# toyotune_3s_coolrunner.net
KiCad netlist of a schematic drawn in EAGLE
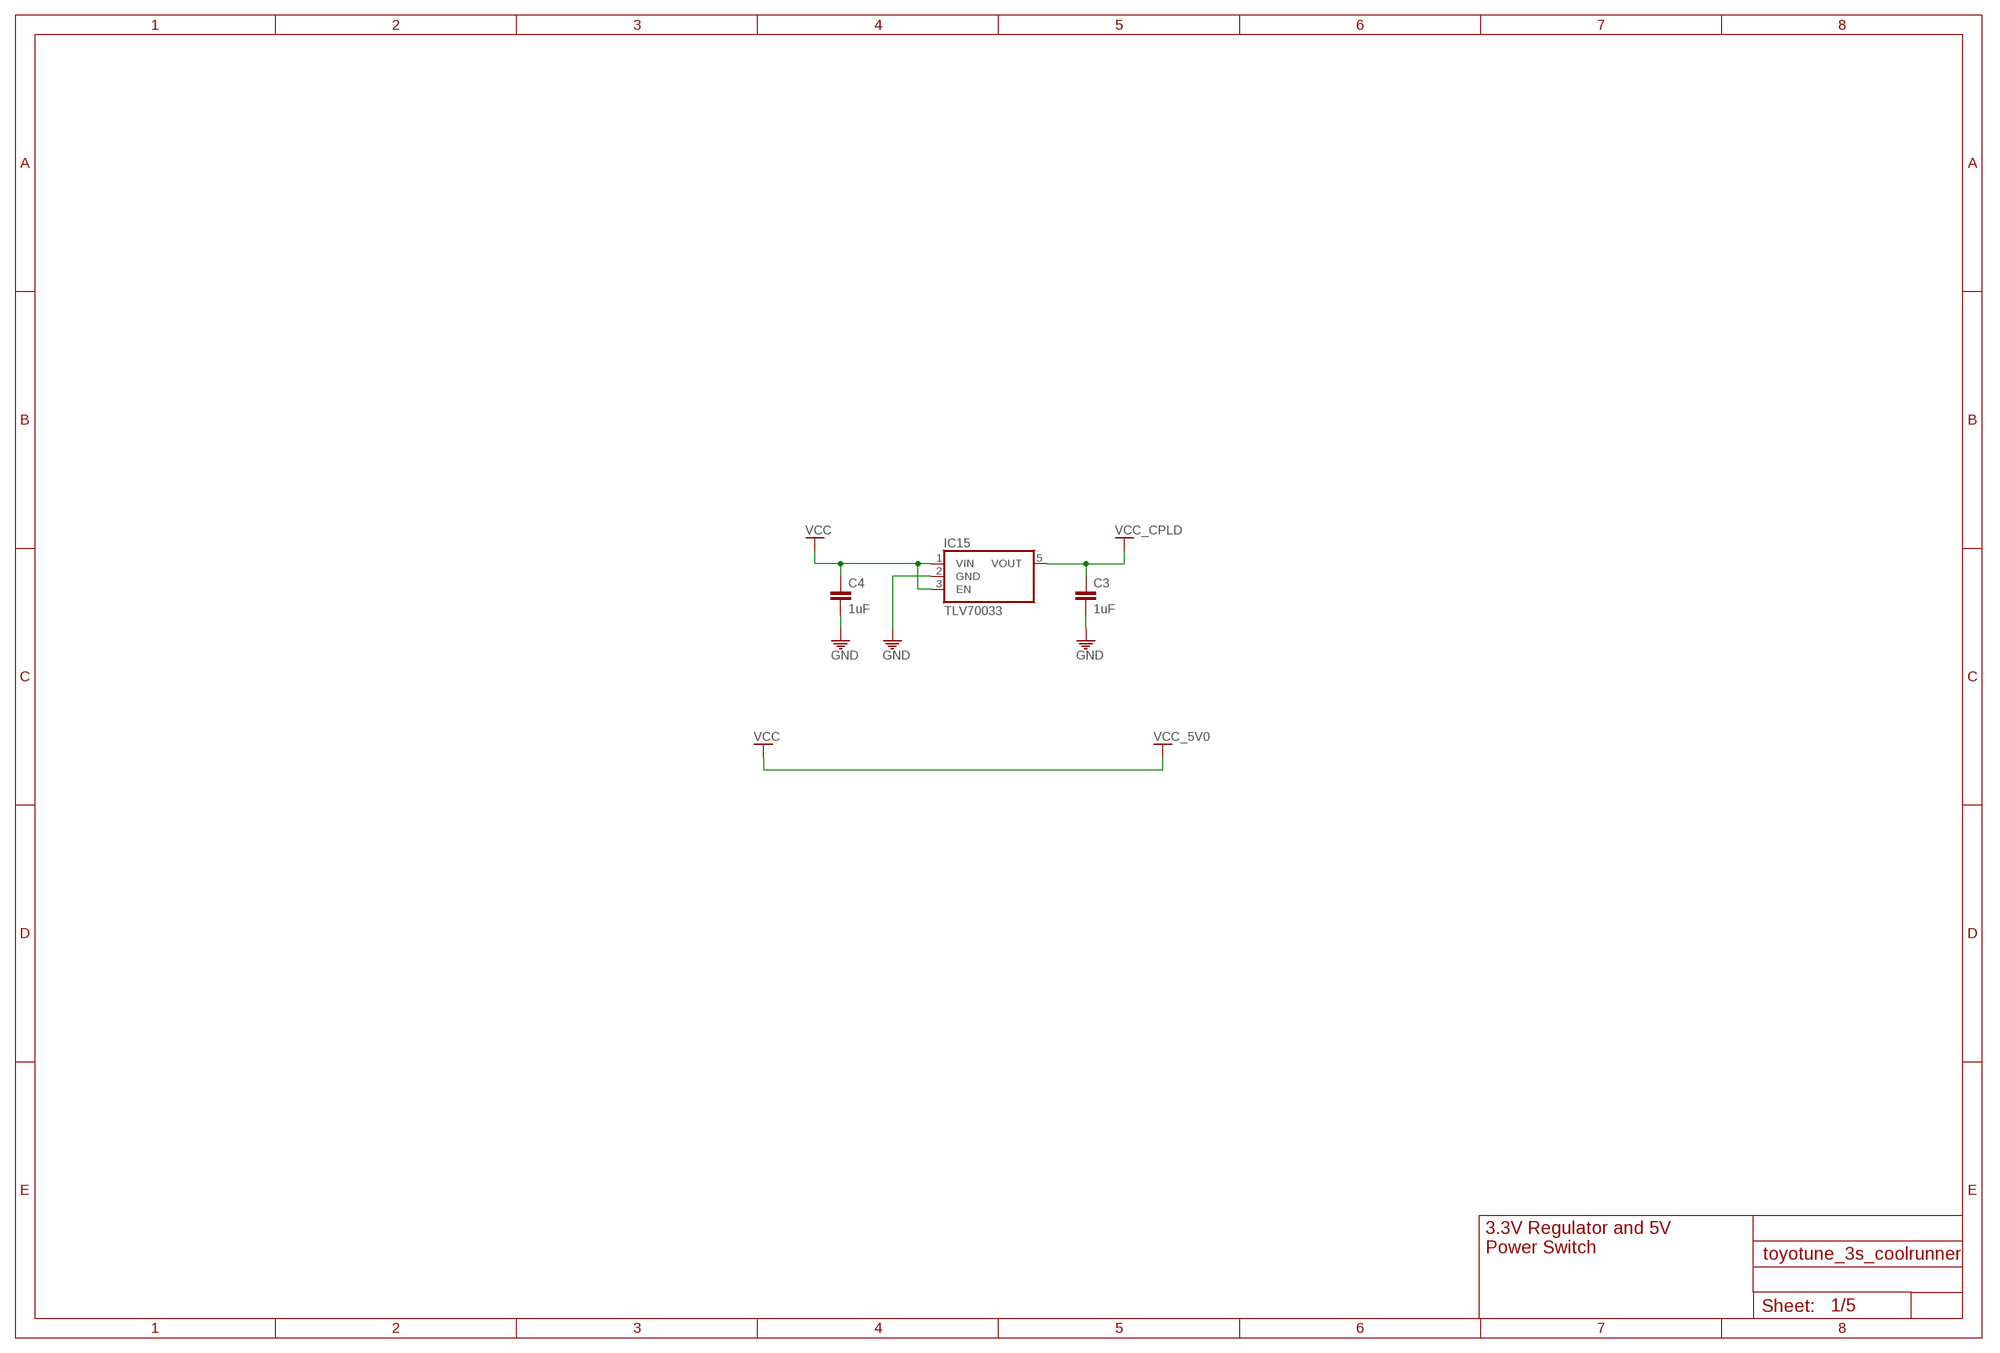
[diagram p0: schematic, sheet 1]
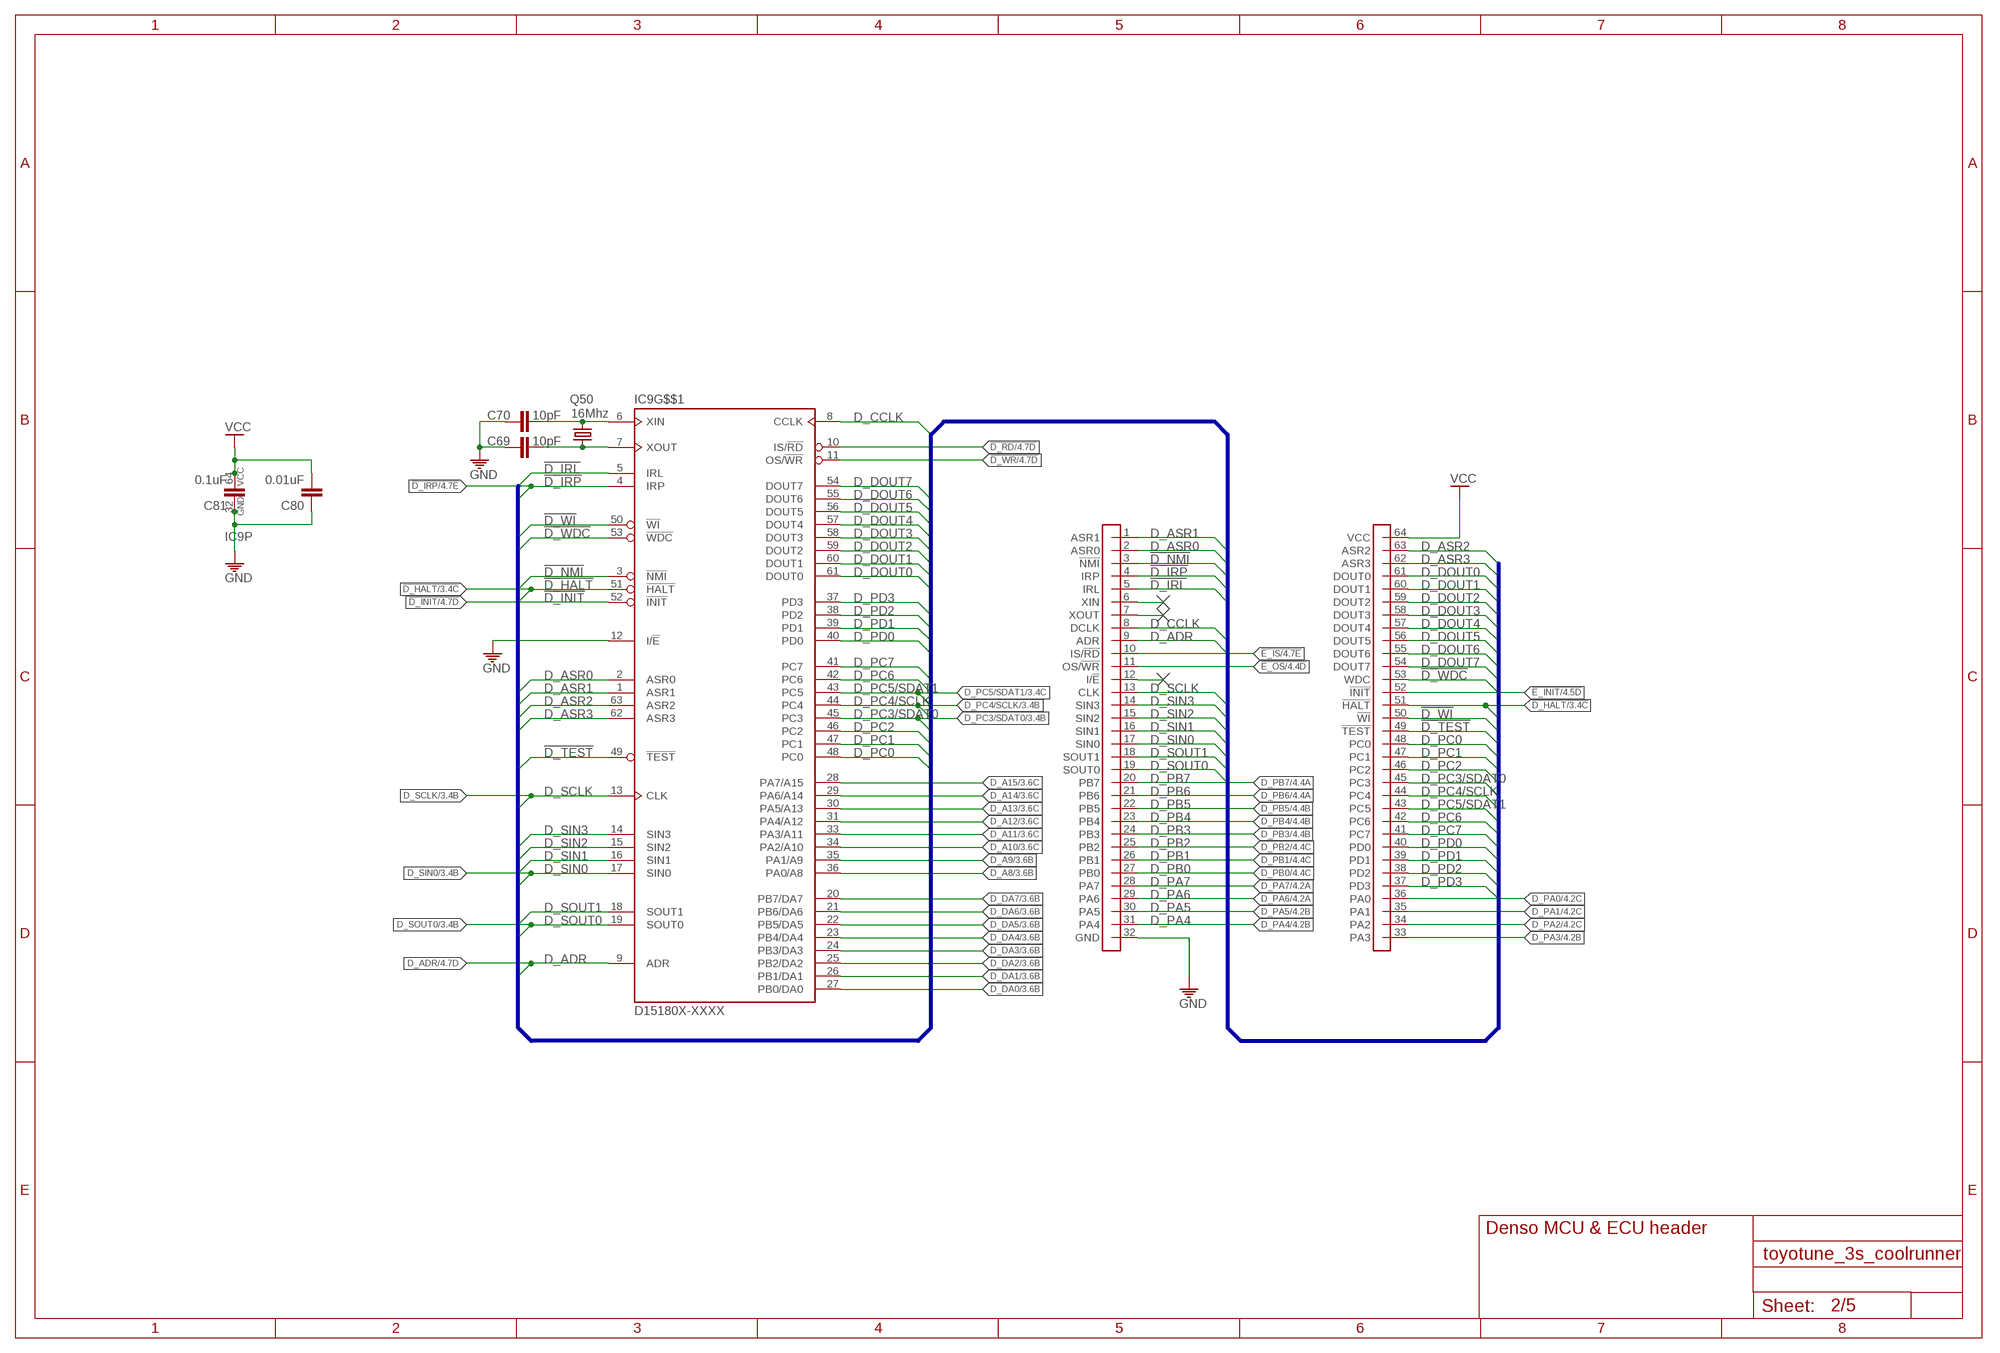
[diagram p1: schematic, sheet 2]
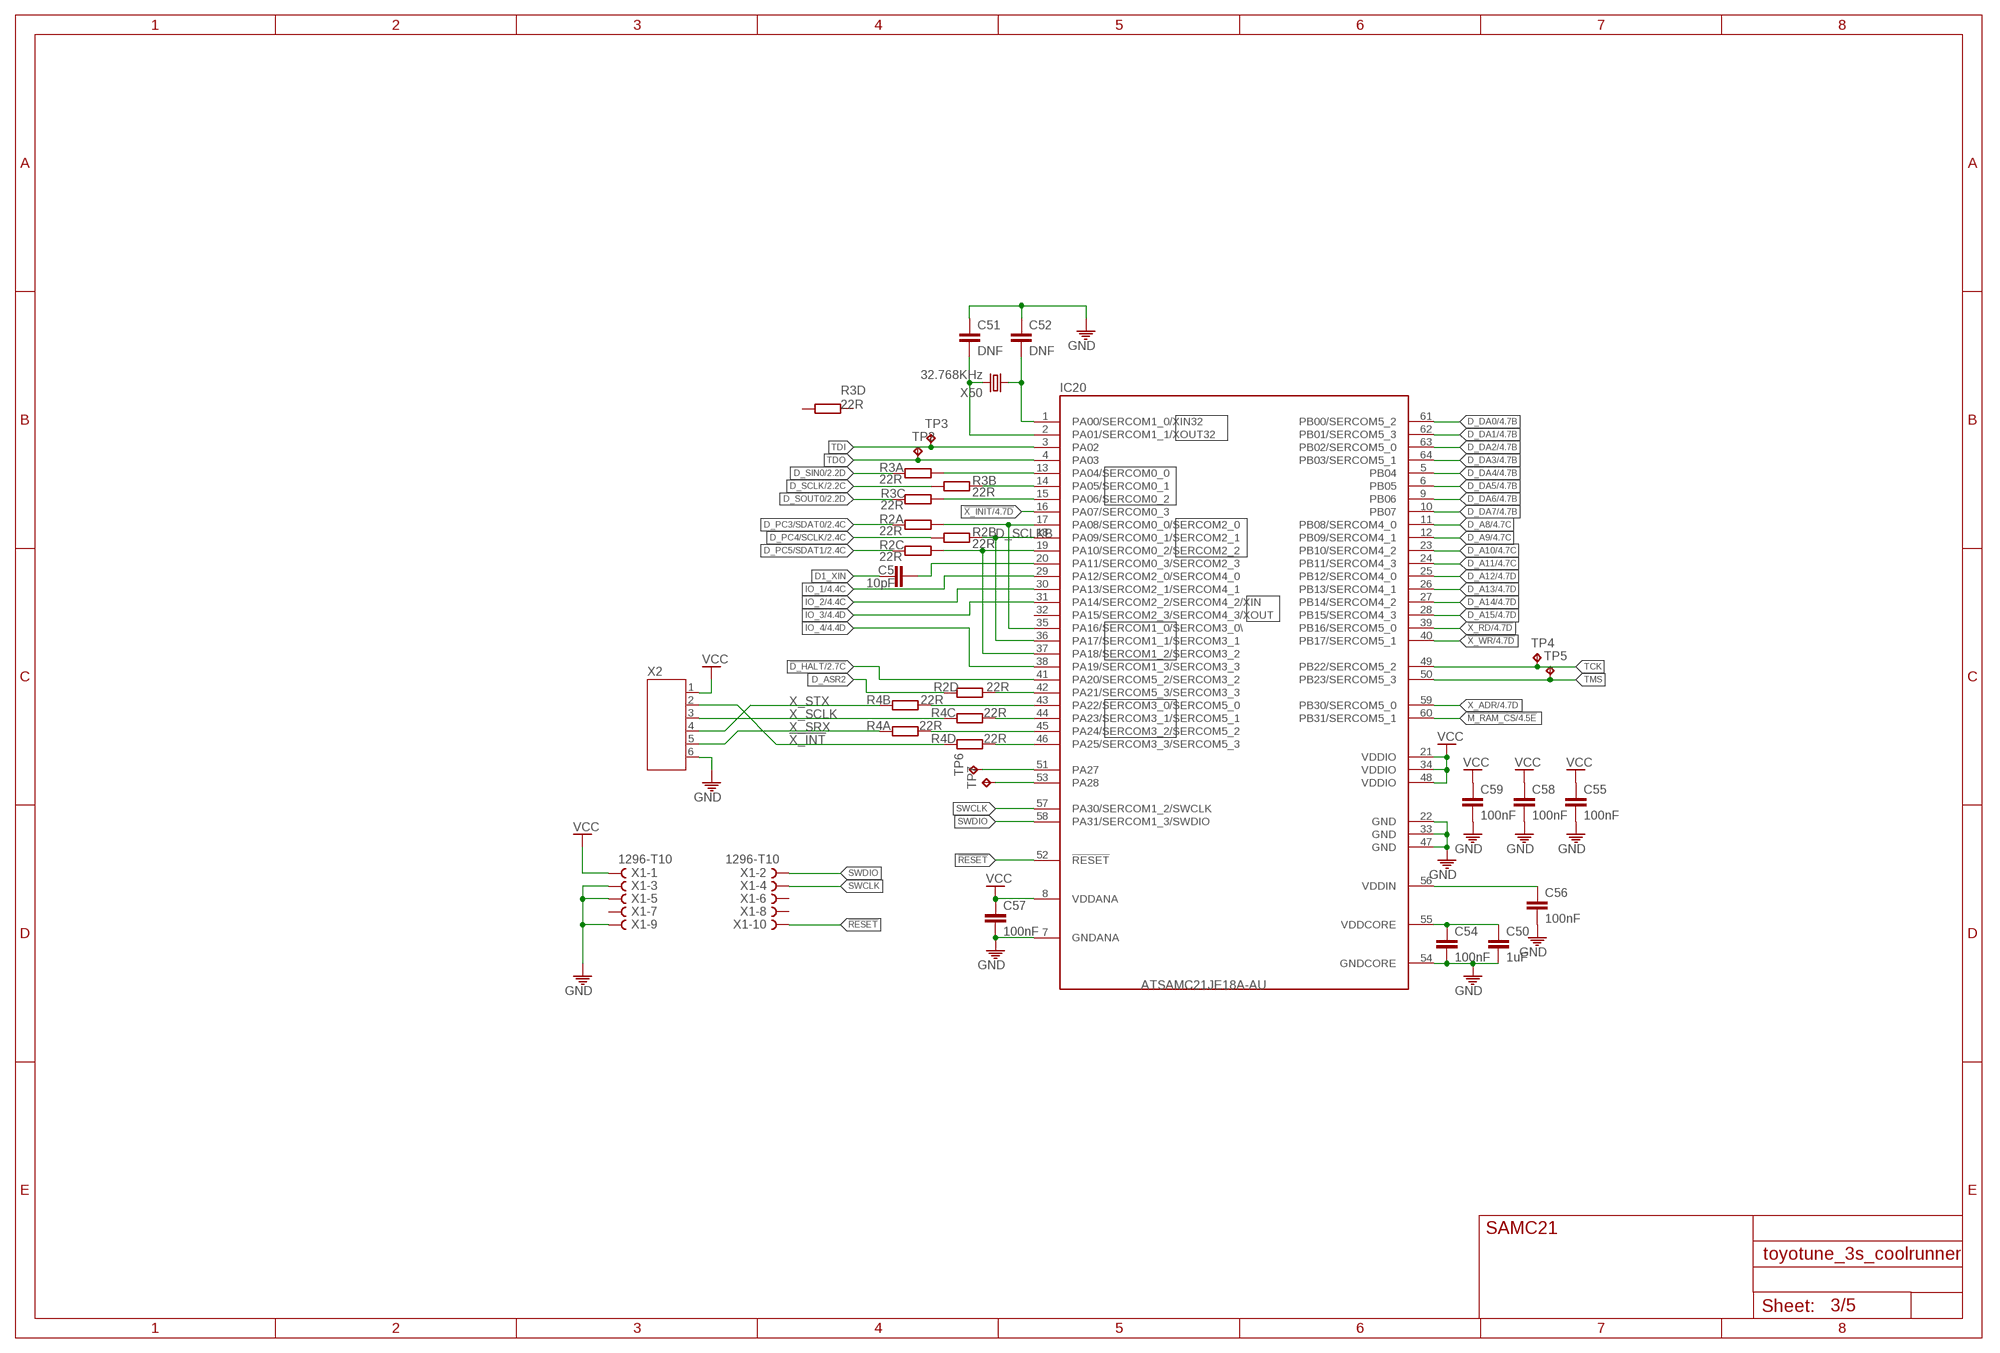
[diagram p2: schematic, sheet 3]
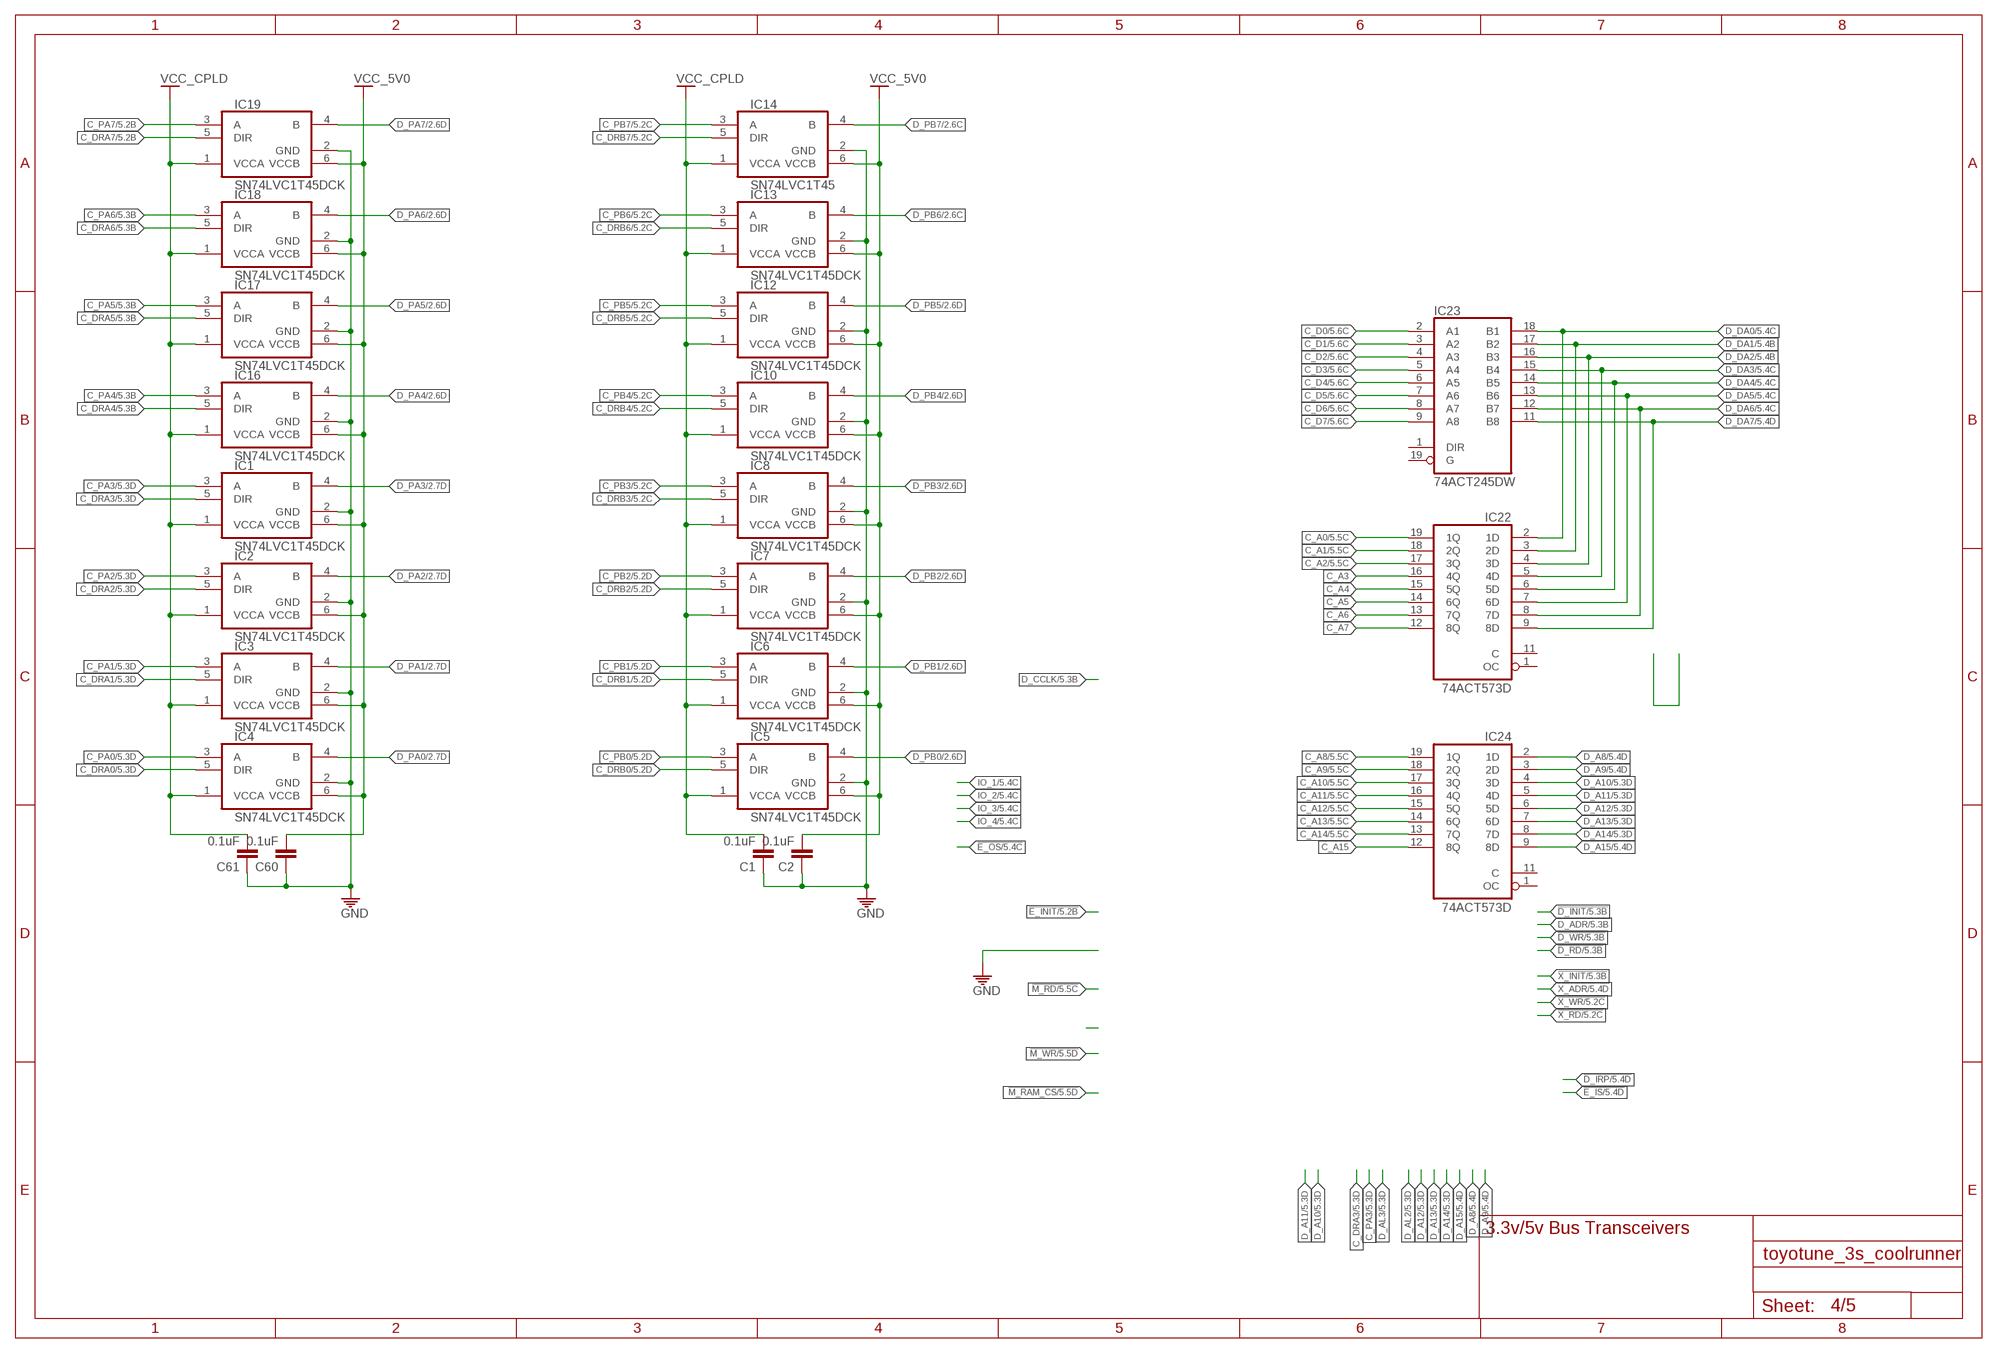
[diagram p3: schematic, sheet 4]
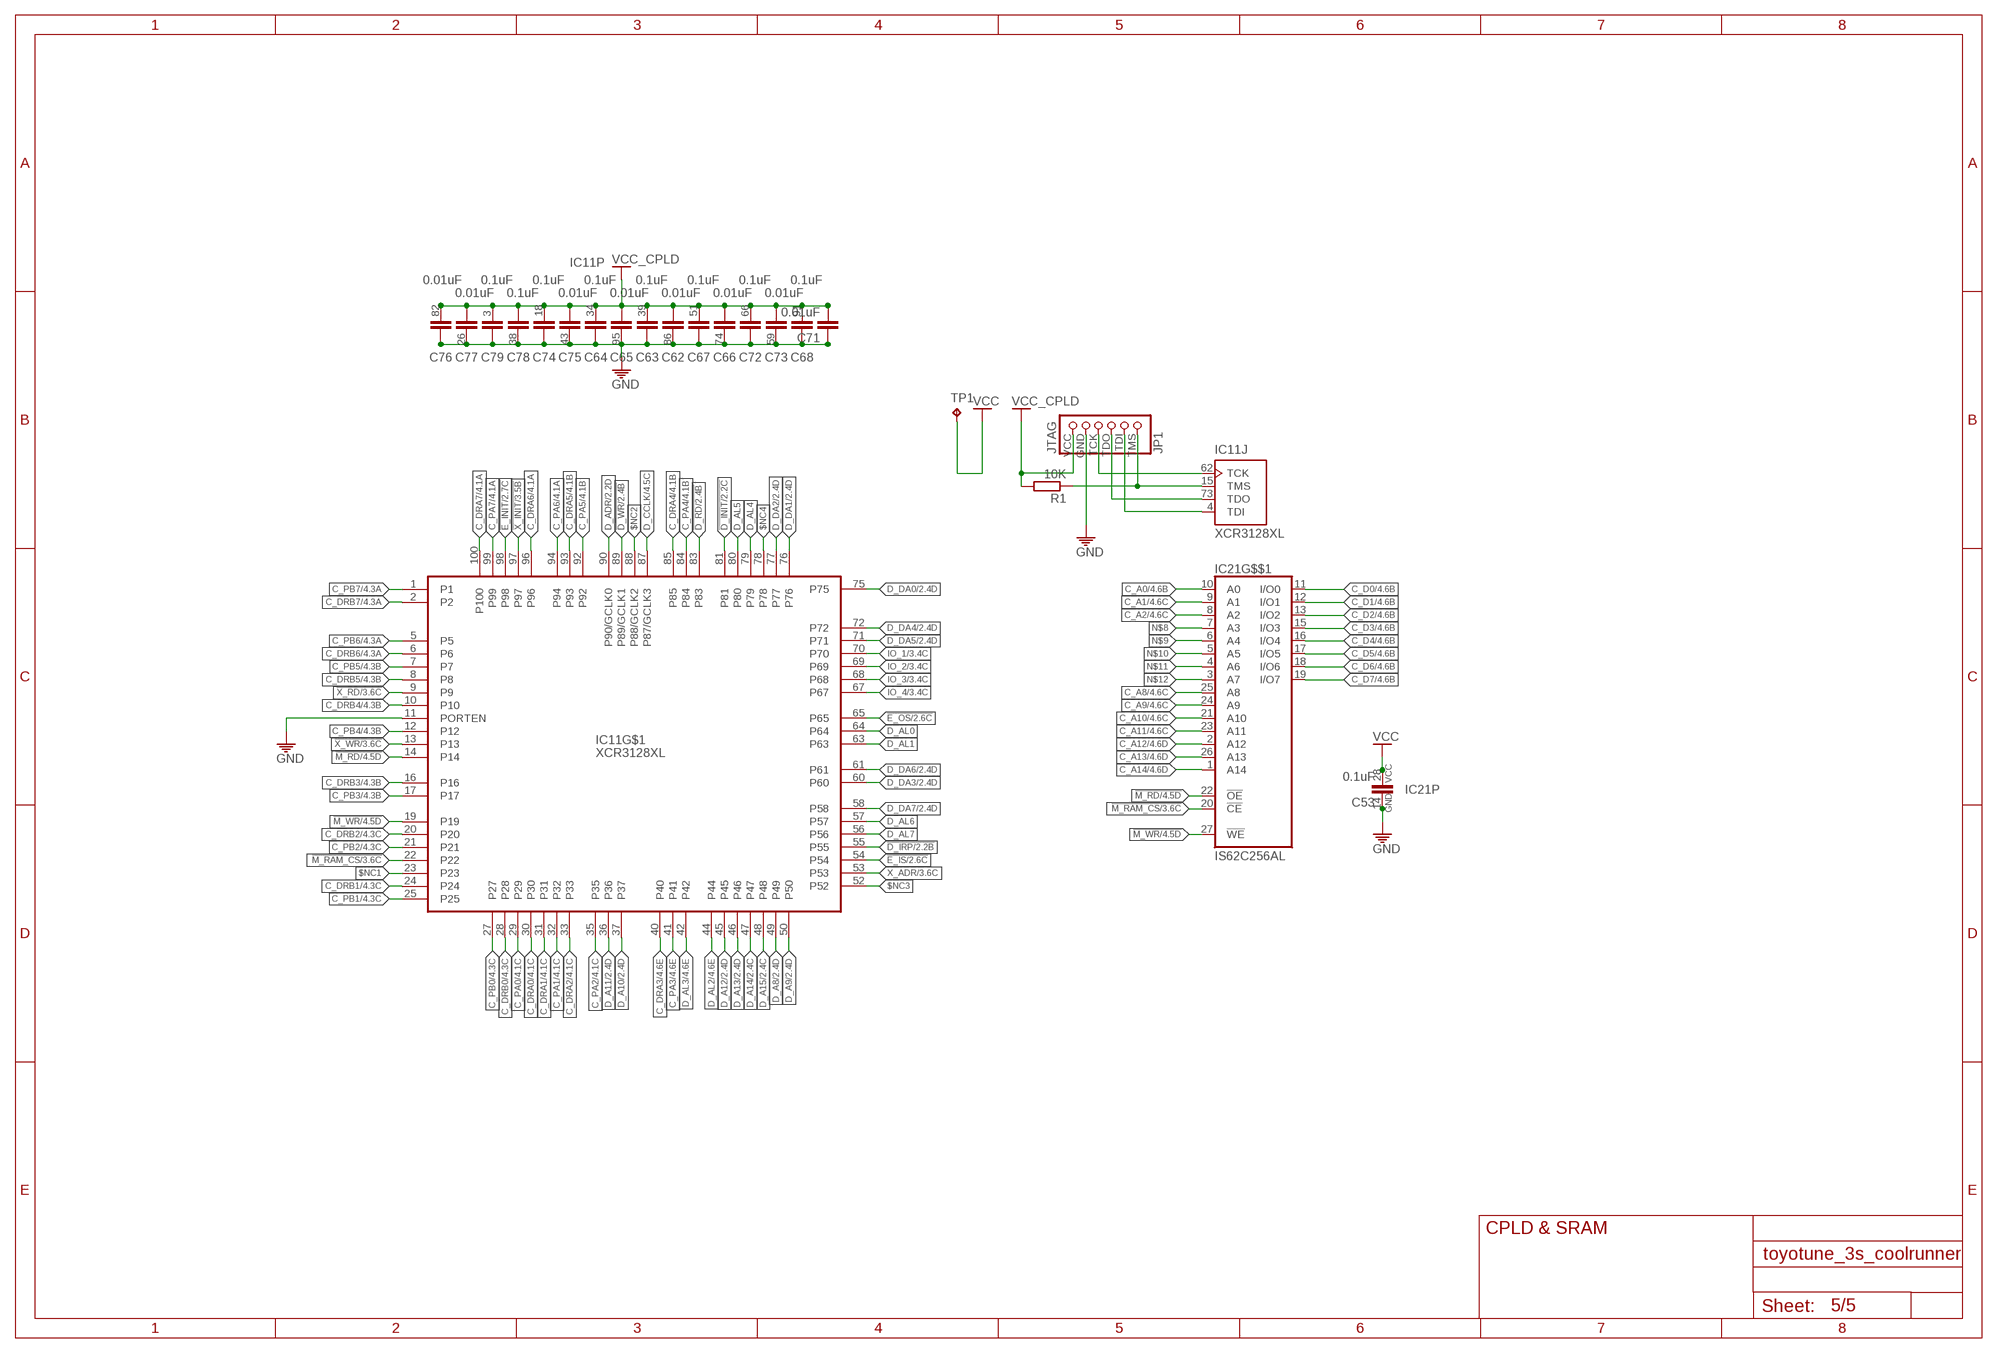
[diagram p4: schematic, sheet 5]

(export (version "E")
  (design (tool "Eeschema 10.0.6"))
  (components
    (comp (ref "C1")
      (value "0.1uF")
      (footprint "eagle-import:C0603")
      (libsource (lib "eagle-import") (part "C-EUC0603"))
    )
    (comp (ref "C2")
      (value "0.1uF")
      (footprint "eagle-import:C0603")
      (libsource (lib "eagle-import") (part "C-EUC0603"))
    )
    (comp (ref "C60")
      (value "0.1uF")
      (footprint "eagle-import:C0603")
      (libsource (lib "eagle-import") (part "C-EUC0603"))
    )
    (comp (ref "C61")
      (value "0.1uF")
      (footprint "eagle-import:C0603")
      (libsource (lib "eagle-import") (part "C-EUC0603"))
    )
    (comp (ref "IC1")
      (value "SN74LVC1T45DCK")
      (footprint "eagle-import:DCK_R-PDSO-G6")
      (libsource (lib "eagle-import") (part "SN74LVC1T45DCK"))
    )
    (comp (ref "IC2")
      (value "SN74LVC1T45DCK")
      (footprint "eagle-import:DCK_R-PDSO-G6")
      (libsource (lib "eagle-import") (part "SN74LVC1T45DCK"))
    )
    (comp (ref "IC3")
      (value "SN74LVC1T45DCK")
      (footprint "eagle-import:DCK_R-PDSO-G6")
      (libsource (lib "eagle-import") (part "SN74LVC1T45DCK"))
    )
    (comp (ref "IC4")
      (value "SN74LVC1T45DCK")
      (footprint "eagle-import:DCK_R-PDSO-G6")
      (libsource (lib "eagle-import") (part "SN74LVC1T45DCK"))
    )
    (comp (ref "IC5")
      (value "SN74LVC1T45DCK")
      (footprint "eagle-import:DCK_R-PDSO-G6")
      (libsource (lib "eagle-import") (part "SN74LVC1T45DCK"))
    )
    (comp (ref "IC6")
      (value "SN74LVC1T45DCK")
      (footprint "eagle-import:DCK_R-PDSO-G6")
      (libsource (lib "eagle-import") (part "SN74LVC1T45DCK"))
    )
    (comp (ref "IC7")
      (value "SN74LVC1T45DCK")
      (footprint "eagle-import:DCK_R-PDSO-G6")
      (libsource (lib "eagle-import") (part "SN74LVC1T45DCK"))
    )
    (comp (ref "IC8")
      (value "SN74LVC1T45DCK")
      (footprint "eagle-import:DCK_R-PDSO-G6")
      (libsource (lib "eagle-import") (part "SN74LVC1T45DCK"))
    )
    (comp (ref "IC10")
      (value "SN74LVC1T45DCK")
      (footprint "eagle-import:DCK_R-PDSO-G6")
      (libsource (lib "eagle-import") (part "SN74LVC1T45DCK"))
    )
    (comp (ref "IC12")
      (value "SN74LVC1T45DCK")
      (footprint "eagle-import:DCK_R-PDSO-G6")
      (libsource (lib "eagle-import") (part "SN74LVC1T45DCK"))
    )
    (comp (ref "IC13")
      (value "SN74LVC1T45DCK")
      (footprint "eagle-import:DCK_R-PDSO-G6")
      (libsource (lib "eagle-import") (part "SN74LVC1T45DCK"))
    )
    (comp (ref "IC14")
      (value "SN74LVC1T45")
      (footprint "eagle-import:DCK_R-PDSO-G6")
      (libsource (lib "eagle-import") (part "SN74LVC1T45DCK"))
    )
    (comp (ref "IC16")
      (value "SN74LVC1T45DCK")
      (footprint "eagle-import:DCK_R-PDSO-G6")
      (libsource (lib "eagle-import") (part "SN74LVC1T45DCK"))
    )
    (comp (ref "IC17")
      (value "SN74LVC1T45DCK")
      (footprint "eagle-import:DCK_R-PDSO-G6")
      (libsource (lib "eagle-import") (part "SN74LVC1T45DCK"))
    )
    (comp (ref "IC18")
      (value "SN74LVC1T45DCK")
      (footprint "eagle-import:DCK_R-PDSO-G6")
      (libsource (lib "eagle-import") (part "SN74LVC1T45DCK"))
    )
    (comp (ref "IC19")
      (value "SN74LVC1T45DCK")
      (footprint "eagle-import:DCK_R-PDSO-G6")
      (libsource (lib "eagle-import") (part "SN74LVC1T45DCK"))
    )
    (comp (ref "IC22")
      (value "74ACT573D")
      (footprint "eagle-import:SO20W")
      (libsource (lib "eagle-import") (part "74573DACT"))
    )
    (comp (ref "IC23")
      (value "74ACT245DW")
      (footprint "eagle-import:SO20W")
      (libsource (lib "eagle-import") (part "74245DWACT"))
    )
    (comp (ref "IC24")
      (value "74ACT573D")
      (footprint "eagle-import:SO20W")
      (libsource (lib "eagle-import") (part "74573DACT"))
    )
    (comp (ref "C3")
      (value "1uF")
      (footprint "eagle-import:C0603")
      (libsource (lib "eagle-import") (part "C-EUC0603"))
    )
    (comp (ref "C4")
      (value "1uF")
      (footprint "eagle-import:C0603")
      (libsource (lib "eagle-import") (part "C-EUC0603"))
    )
    (comp (ref "IC15")
      (value "TLV70033")
      (footprint "eagle-import:DDC_R-PDSO-G5")
      (libsource (lib "eagle-import") (part "TLV70033"))
    )
    (comp (ref "C53")
      (value "0.1uF")
      (footprint "eagle-import:C0603")
      (libsource (lib "eagle-import") (part "C-EUC0603"))
    )
    (comp (ref "C62")
      (value "0.01uF")
      (footprint "eagle-import:C0603")
      (libsource (lib "eagle-import") (part "C-EUC0603"))
    )
    (comp (ref "C63")
      (value "0.1uF")
      (footprint "eagle-import:C0603")
      (libsource (lib "eagle-import") (part "C-EUC0603"))
    )
    (comp (ref "C64")
      (value "0.1uF")
      (footprint "eagle-import:C0603")
      (libsource (lib "eagle-import") (part "C-EUC0603"))
    )
    (comp (ref "C65")
      (value "0.01uF")
      (footprint "eagle-import:C0603")
      (libsource (lib "eagle-import") (part "C-EUC0603"))
    )
    (comp (ref "C66")
      (value "0.01uF")
      (footprint "eagle-import:C0603")
      (libsource (lib "eagle-import") (part "C-EUC0603"))
    )
    (comp (ref "C67")
      (value "0.1uF")
      (footprint "eagle-import:C0603")
      (libsource (lib "eagle-import") (part "C-EUC0603"))
    )
    (comp (ref "C68")
      (value "0.1uF")
      (footprint "eagle-import:C0603")
      (libsource (lib "eagle-import") (part "C-EUC0603"))
    )
    (comp (ref "C71")
      (value "0.01uF")
      (footprint "eagle-import:C0603")
      (libsource (lib "eagle-import") (part "C-EUC0603"))
    )
    (comp (ref "C72")
      (value "0.1uF")
      (footprint "eagle-import:C0603")
      (libsource (lib "eagle-import") (part "C-EUC0603"))
    )
    (comp (ref "C73")
      (value "0.01uF")
      (footprint "eagle-import:C0603")
      (libsource (lib "eagle-import") (part "C-EUC0603"))
    )
    (comp (ref "C74")
      (value "0.1uF")
      (footprint "eagle-import:C0603")
      (libsource (lib "eagle-import") (part "C-EUC0603"))
    )
    (comp (ref "C75")
      (value "0.01uF")
      (footprint "eagle-import:C0603")
      (libsource (lib "eagle-import") (part "C-EUC0603"))
    )
    (comp (ref "C76")
      (value "0.01uF")
      (footprint "eagle-import:C0603")
      (libsource (lib "eagle-import") (part "C-EUC0603"))
    )
    (comp (ref "C77")
      (value "0.01uF")
      (footprint "eagle-import:C0603")
      (libsource (lib "eagle-import") (part "C-EUC0603"))
    )
    (comp (ref "C78")
      (value "0.1uF")
      (footprint "eagle-import:C0603")
      (libsource (lib "eagle-import") (part "C-EUC0603"))
    )
    (comp (ref "C79")
      (value "0.1uF")
      (footprint "eagle-import:C0603")
      (libsource (lib "eagle-import") (part "C-EUC0603"))
    )
    (comp (ref "IC11")
      (value "XCR3128XL")
      (footprint "eagle-import:VQ100")
      (libsource (lib "eagle-import") (part "XCR3128XL"))
    )
    (comp (ref "IC21")
      (value "IS62C256AL")
      (footprint "eagle-import:TSOP28")
      (libsource (lib "eagle-import") (part "IS62C256AL"))
    )
    (comp (ref "JP1")
      (value "JTAG")
      (footprint "eagle-import:1X06_SMD")
      (libsource (lib "eagle-import") (part "JTAG_HEADERS"))
    )
    (comp (ref "R1")
      (value "10K")
      (footprint "eagle-import:R0603")
      (libsource (lib "eagle-import") (part "R-EU_R0603"))
    )
    (comp (ref "TP1")
      (value "TPTP13R")
      (footprint "eagle-import:TP13R")
      (libsource (lib "eagle-import") (part "TPTP13R"))
    )
    (comp (ref "C5")
      (value "10pF")
      (footprint "eagle-import:C0603")
      (libsource (lib "eagle-import") (part "C-EUC0603"))
    )
    (comp (ref "C50")
      (value "1uF")
      (footprint "eagle-import:C0603")
      (libsource (lib "eagle-import") (part "C-EUC0603"))
    )
    (comp (ref "C51")
      (value "DNF")
      (footprint "eagle-import:C0603")
      (libsource (lib "eagle-import") (part "C-EUC0603"))
    )
    (comp (ref "C52")
      (value "DNF")
      (footprint "eagle-import:C0603")
      (libsource (lib "eagle-import") (part "C-EUC0603"))
    )
    (comp (ref "C54")
      (value "100nF")
      (footprint "eagle-import:C0603")
      (libsource (lib "eagle-import") (part "C-EUC0603"))
    )
    (comp (ref "C55")
      (value "100nF")
      (footprint "eagle-import:C0603")
      (libsource (lib "eagle-import") (part "C-EUC0603"))
    )
    (comp (ref "C56")
      (value "100nF")
      (footprint "eagle-import:C0603")
      (libsource (lib "eagle-import") (part "C-EUC0603"))
    )
    (comp (ref "C57")
      (value "100nF")
      (footprint "eagle-import:C0603")
      (libsource (lib "eagle-import") (part "C-EUC0603"))
    )
    (comp (ref "C58")
      (value "100nF")
      (footprint "eagle-import:C0603")
      (libsource (lib "eagle-import") (part "C-EUC0603"))
    )
    (comp (ref "C59")
      (value "100nF")
      (footprint "eagle-import:C0603")
      (libsource (lib "eagle-import") (part "C-EUC0603"))
    )
    (comp (ref "IC20")
      (value "ATSAMC21JE18A-AU")
      (footprint "eagle-import:TQFP64-05")
      (libsource (lib "eagle-import") (part "ATSAMC21JE18A-AU"))
    )
    (comp (ref "R2")
      (value "22R")
      (footprint "eagle-import:CAT16-J4")
      (libsource (lib "eagle-import") (part "CAT16-J4"))
    )
    (comp (ref "R3")
      (value "22R")
      (footprint "eagle-import:CAT16-J4")
      (libsource (lib "eagle-import") (part "CAT16-J4"))
    )
    (comp (ref "R4")
      (value "22R")
      (footprint "eagle-import:CAT16-J4")
      (libsource (lib "eagle-import") (part "CAT16-J4"))
    )
    (comp (ref "TP2")
      (value "TPTP08R")
      (footprint "eagle-import:TP08R")
      (libsource (lib "eagle-import") (part "TPTP08R"))
    )
    (comp (ref "TP3")
      (value "TPTP08R")
      (footprint "eagle-import:TP08R")
      (libsource (lib "eagle-import") (part "TPTP08R"))
    )
    (comp (ref "TP4")
      (value "TPTP08R")
      (footprint "eagle-import:TP08R")
      (libsource (lib "eagle-import") (part "TPTP08R"))
    )
    (comp (ref "TP5")
      (value "TPTP08R")
      (footprint "eagle-import:TP08R")
      (libsource (lib "eagle-import") (part "TPTP08R"))
    )
    (comp (ref "TP6")
      (value "TPTP08R")
      (footprint "eagle-import:TP08R")
      (libsource (lib "eagle-import") (part "TPTP08R"))
    )
    (comp (ref "TP7")
      (value "TPTP08R")
      (footprint "eagle-import:TP08R")
      (libsource (lib "eagle-import") (part "TPTP08R"))
    )
    (comp (ref "X1")
      (value "1296-T10")
      (footprint "eagle-import:1296-10")
      (libsource (lib "eagle-import") (part "1296-T10"))
    )
    (comp (ref "X2")
      (value "JST-PH6")
      (footprint "eagle-import:JST-PH6")
      (libsource (lib "eagle-import") (part "JST-PH6"))
    )
    (comp (ref "X50")
      (value "32.768KHz")
      (footprint "eagle-import:3.2X1.5-2-PAD")
      (libsource (lib "eagle-import") (part "CRYSTALS-NOGND-CFPX-217"))
    )
    (comp (ref "C69")
      (value "10pF")
      (footprint "eagle-import:C0603")
      (libsource (lib "eagle-import") (part "C-EUC0603"))
    )
    (comp (ref "C70")
      (value "10pF")
      (footprint "eagle-import:C0603")
      (libsource (lib "eagle-import") (part "C-EUC0603"))
    )
    (comp (ref "C80")
      (value "0.01uF")
      (footprint "eagle-import:C0603")
      (libsource (lib "eagle-import") (part "C-EUC0603"))
    )
    (comp (ref "C81")
      (value "0.1uF")
      (footprint "eagle-import:C0603")
      (libsource (lib "eagle-import") (part "C-EUC0603"))
    )
    (comp (ref "IC9")
      (value "D15180X-XXXX")
      (footprint "eagle-import:SDIP-64")
      (libsource (lib "eagle-import") (part "D151803-9661"))
    )
    (comp (ref "Q50")
      (value "16Mhz")
      (footprint "eagle-import:CRYSTAL-SMD-5X3")
      (libsource (lib "eagle-import") (part "CRYSTAL5X3"))
    )
    (comp (ref "U1")
      (value "D151803-CONN")
      (footprint "eagle-import:SDIP-64-CONN")
      (libsource (lib "eagle-import") (part "D151803-CONN"))
    )
  )
  (nets
    (net (code "1") (name "$NC1") (class "Default")
      (node (ref "IC11") (pin "23") (pinfunction "P23_23") (pintype "bidirectional"))
    )
    (net (code "2") (name "$NC2") (class "Default")
      (node (ref "IC11") (pin "88") (pinfunction "P88/GCLK2_88") (pintype "input"))
    )
    (net (code "3") (name "$NC3") (class "Default")
      (node (ref "IC11") (pin "52") (pinfunction "P52_52") (pintype "bidirectional"))
    )
    (net (code "4") (name "$NC4") (class "Default")
      (node (ref "IC11") (pin "78") (pinfunction "P78_78") (pintype "bidirectional"))
    )
    (net (code "5") (name "C_A0") (class "Default")
      (node (ref "IC21") (pin "10") (pinfunction "A0_10") (pintype "input"))
      (node (ref "IC22") (pin "19") (pinfunction "1Q_19") (pintype "tri_state"))
    )
    (net (code "6") (name "C_A1") (class "Default")
      (node (ref "IC21") (pin "9") (pinfunction "A1_9") (pintype "input"))
      (node (ref "IC22") (pin "18") (pinfunction "2Q_18") (pintype "tri_state"))
    )
    (net (code "7") (name "C_A2") (class "Default")
      (node (ref "IC21") (pin "8") (pinfunction "A2_8") (pintype "input"))
      (node (ref "IC22") (pin "17") (pinfunction "3Q_17") (pintype "tri_state"))
    )
    (net (code "8") (name "C_A3") (class "Default")
      (node (ref "IC22") (pin "16") (pinfunction "4Q_16") (pintype "tri_state"))
    )
    (net (code "9") (name "C_A4") (class "Default")
      (node (ref "IC22") (pin "15") (pinfunction "5Q_15") (pintype "tri_state"))
    )
    (net (code "10") (name "C_A5") (class "Default")
      (node (ref "IC22") (pin "14") (pinfunction "6Q_14") (pintype "tri_state"))
    )
    (net (code "11") (name "C_A6") (class "Default")
      (node (ref "IC22") (pin "13") (pinfunction "7Q_13") (pintype "tri_state"))
    )
    (net (code "12") (name "C_A7") (class "Default")
      (node (ref "IC22") (pin "12") (pinfunction "8Q_12") (pintype "tri_state"))
    )
    (net (code "13") (name "C_A8") (class "Default")
      (node (ref "IC21") (pin "25") (pinfunction "A8_25") (pintype "input"))
      (node (ref "IC24") (pin "19") (pinfunction "1Q_19") (pintype "tri_state"))
    )
    (net (code "14") (name "C_A9") (class "Default")
      (node (ref "IC21") (pin "24") (pinfunction "A9_24") (pintype "input"))
      (node (ref "IC24") (pin "18") (pinfunction "2Q_18") (pintype "tri_state"))
    )
    (net (code "15") (name "C_A10") (class "Default")
      (node (ref "IC21") (pin "21") (pinfunction "A10_21") (pintype "input"))
      (node (ref "IC24") (pin "17") (pinfunction "3Q_17") (pintype "tri_state"))
    )
    (net (code "16") (name "C_A11") (class "Default")
      (node (ref "IC21") (pin "23") (pinfunction "A11_23") (pintype "input"))
      (node (ref "IC24") (pin "16") (pinfunction "4Q_16") (pintype "tri_state"))
    )
    (net (code "17") (name "C_A12") (class "Default")
      (node (ref "IC21") (pin "2") (pinfunction "A12_2") (pintype "input"))
      (node (ref "IC24") (pin "15") (pinfunction "5Q_15") (pintype "tri_state"))
    )
    (net (code "18") (name "C_A13") (class "Default")
      (node (ref "IC21") (pin "26") (pinfunction "A13_26") (pintype "input"))
      (node (ref "IC24") (pin "14") (pinfunction "6Q_14") (pintype "tri_state"))
    )
    (net (code "19") (name "C_A14") (class "Default")
      (node (ref "IC21") (pin "1") (pinfunction "A14_1") (pintype "input"))
      (node (ref "IC24") (pin "13") (pinfunction "7Q_13") (pintype "tri_state"))
    )
    (net (code "20") (name "C_A15") (class "Default")
      (node (ref "IC24") (pin "12") (pinfunction "8Q_12") (pintype "tri_state"))
    )
    (net (code "21") (name "C_D0") (class "Default")
      (node (ref "IC21") (pin "11") (pinfunction "I/O0_11") (pintype "bidirectional"))
      (node (ref "IC23") (pin "2") (pinfunction "A1_2") (pintype "bidirectional"))
    )
    (net (code "22") (name "C_D1") (class "Default")
      (node (ref "IC21") (pin "12") (pinfunction "I/O1_12") (pintype "bidirectional"))
      (node (ref "IC23") (pin "3") (pinfunction "A2_3") (pintype "bidirectional"))
    )
    (net (code "23") (name "C_D2") (class "Default")
      (node (ref "IC21") (pin "13") (pinfunction "I/O2_13") (pintype "bidirectional"))
      (node (ref "IC23") (pin "4") (pinfunction "A3_4") (pintype "bidirectional"))
    )
    (net (code "24") (name "C_D3") (class "Default")
      (node (ref "IC21") (pin "15") (pinfunction "I/O3_15") (pintype "bidirectional"))
      (node (ref "IC23") (pin "5") (pinfunction "A4_5") (pintype "bidirectional"))
    )
    (net (code "25") (name "C_D4") (class "Default")
      (node (ref "IC21") (pin "16") (pinfunction "I/O4_16") (pintype "bidirectional"))
      (node (ref "IC23") (pin "6") (pinfunction "A5_6") (pintype "bidirectional"))
    )
    (net (code "26") (name "C_D5") (class "Default")
      (node (ref "IC21") (pin "17") (pinfunction "I/O5_17") (pintype "bidirectional"))
      (node (ref "IC23") (pin "7") (pinfunction "A6_7") (pintype "bidirectional"))
    )
    (net (code "27") (name "C_D6") (class "Default")
      (node (ref "IC21") (pin "18") (pinfunction "I/O6_18") (pintype "bidirectional"))
      (node (ref "IC23") (pin "8") (pinfunction "A7_8") (pintype "bidirectional"))
    )
    (net (code "28") (name "C_D7") (class "Default")
      (node (ref "IC21") (pin "19") (pinfunction "I/O7_19") (pintype "bidirectional"))
      (node (ref "IC23") (pin "9") (pinfunction "A8_9") (pintype "bidirectional"))
    )
    (net (code "29") (name "C_DRA0") (class "Default")
      (node (ref "IC11") (pin "30") (pinfunction "P30_30") (pintype "bidirectional"))
      (node (ref "IC4") (pin "5") (pinfunction "DIR_5") (pintype "input"))
    )
    (net (code "30") (name "C_DRA1") (class "Default")
      (node (ref "IC11") (pin "31") (pinfunction "P31_31") (pintype "bidirectional"))
      (node (ref "IC3") (pin "5") (pinfunction "DIR_5") (pintype "input"))
    )
    (net (code "31") (name "C_DRA2") (class "Default")
      (node (ref "IC11") (pin "33") (pinfunction "P33_33") (pintype "bidirectional"))
      (node (ref "IC2") (pin "5") (pinfunction "DIR_5") (pintype "input"))
    )
    (net (code "32") (name "C_DRA3") (class "Default")
      (node (ref "IC1") (pin "5") (pinfunction "DIR_5") (pintype "input"))
      (node (ref "IC11") (pin "40") (pinfunction "P40_40") (pintype "bidirectional"))
    )
    (net (code "33") (name "C_DRA4") (class "Default")
      (node (ref "IC11") (pin "85") (pinfunction "P85_85") (pintype "bidirectional"))
      (node (ref "IC16") (pin "5") (pinfunction "DIR_5") (pintype "input"))
    )
    (net (code "34") (name "C_DRA5") (class "Default")
      (node (ref "IC11") (pin "93") (pinfunction "P93_93") (pintype "bidirectional"))
      (node (ref "IC17") (pin "5") (pinfunction "DIR_5") (pintype "input"))
    )
    (net (code "35") (name "C_DRA6") (class "Default")
      (node (ref "IC11") (pin "96") (pinfunction "P96_96") (pintype "bidirectional"))
      (node (ref "IC18") (pin "5") (pinfunction "DIR_5") (pintype "input"))
    )
    (net (code "36") (name "C_DRA7") (class "Default")
      (node (ref "IC11") (pin "100") (pinfunction "P100_100") (pintype "bidirectional"))
      (node (ref "IC19") (pin "5") (pinfunction "DIR_5") (pintype "input"))
    )
    (net (code "37") (name "C_DRB0") (class "Default")
      (node (ref "IC11") (pin "28") (pinfunction "P28_28") (pintype "bidirectional"))
      (node (ref "IC5") (pin "5") (pinfunction "DIR_5") (pintype "input"))
    )
    (net (code "38") (name "C_DRB1") (class "Default")
      (node (ref "IC11") (pin "24") (pinfunction "P24_24") (pintype "bidirectional"))
      (node (ref "IC6") (pin "5") (pinfunction "DIR_5") (pintype "input"))
    )
    (net (code "39") (name "C_DRB2") (class "Default")
      (node (ref "IC11") (pin "20") (pinfunction "P20_20") (pintype "bidirectional"))
      (node (ref "IC7") (pin "5") (pinfunction "DIR_5") (pintype "input"))
    )
    (net (code "40") (name "C_DRB3") (class "Default")
      (node (ref "IC11") (pin "16") (pinfunction "P16_16") (pintype "bidirectional"))
      (node (ref "IC8") (pin "5") (pinfunction "DIR_5") (pintype "input"))
    )
    (net (code "41") (name "C_DRB4") (class "Default")
      (node (ref "IC10") (pin "5") (pinfunction "DIR_5") (pintype "input"))
      (node (ref "IC11") (pin "10") (pinfunction "P10_10") (pintype "bidirectional"))
    )
    (net (code "42") (name "C_DRB5") (class "Default")
      (node (ref "IC11") (pin "8") (pinfunction "P8_8") (pintype "bidirectional"))
      (node (ref "IC12") (pin "5") (pinfunction "DIR_5") (pintype "input"))
    )
    (net (code "43") (name "C_DRB6") (class "Default")
      (node (ref "IC11") (pin "6") (pinfunction "P6_6") (pintype "bidirectional"))
      (node (ref "IC13") (pin "5") (pinfunction "DIR_5") (pintype "input"))
    )
    (net (code "44") (name "C_DRB7") (class "Default")
      (node (ref "IC11") (pin "2") (pinfunction "P2_2") (pintype "bidirectional"))
      (node (ref "IC14") (pin "5") (pinfunction "DIR_5") (pintype "input"))
    )
    (net (code "45") (name "C_PA0") (class "Default")
      (node (ref "IC11") (pin "29") (pinfunction "P29_29") (pintype "bidirectional"))
      (node (ref "IC4") (pin "3") (pinfunction "A_3") (pintype "bidirectional"))
    )
    (net (code "46") (name "C_PA1") (class "Default")
      (node (ref "IC11") (pin "32") (pinfunction "P32_32") (pintype "bidirectional"))
      (node (ref "IC3") (pin "3") (pinfunction "A_3") (pintype "bidirectional"))
    )
    (net (code "47") (name "C_PA2") (class "Default")
      (node (ref "IC11") (pin "35") (pinfunction "P35_35") (pintype "bidirectional"))
      (node (ref "IC2") (pin "3") (pinfunction "A_3") (pintype "bidirectional"))
    )
    (net (code "48") (name "C_PA3") (class "Default")
      (node (ref "IC1") (pin "3") (pinfunction "A_3") (pintype "bidirectional"))
      (node (ref "IC11") (pin "41") (pinfunction "P41_41") (pintype "bidirectional"))
    )
    (net (code "49") (name "C_PA4") (class "Default")
      (node (ref "IC11") (pin "84") (pinfunction "P84_84") (pintype "bidirectional"))
      (node (ref "IC16") (pin "3") (pinfunction "A_3") (pintype "bidirectional"))
    )
    (net (code "50") (name "C_PA5") (class "Default")
      (node (ref "IC11") (pin "92") (pinfunction "P92_92") (pintype "bidirectional"))
      (node (ref "IC17") (pin "3") (pinfunction "A_3") (pintype "bidirectional"))
    )
    (net (code "51") (name "C_PA6") (class "Default")
      (node (ref "IC11") (pin "94") (pinfunction "P94_94") (pintype "bidirectional"))
      (node (ref "IC18") (pin "3") (pinfunction "A_3") (pintype "bidirectional"))
    )
    (net (code "52") (name "C_PA7") (class "Default")
      (node (ref "IC11") (pin "99") (pinfunction "P99_99") (pintype "bidirectional"))
      (node (ref "IC19") (pin "3") (pinfunction "A_3") (pintype "bidirectional"))
    )
    (net (code "53") (name "C_PB0") (class "Default")
      (node (ref "IC11") (pin "27") (pinfunction "P27_27") (pintype "bidirectional"))
      (node (ref "IC5") (pin "3") (pinfunction "A_3") (pintype "bidirectional"))
    )
    (net (code "54") (name "C_PB1") (class "Default")
      (node (ref "IC11") (pin "25") (pinfunction "P25_25") (pintype "bidirectional"))
      (node (ref "IC6") (pin "3") (pinfunction "A_3") (pintype "bidirectional"))
    )
    (net (code "55") (name "C_PB2") (class "Default")
      (node (ref "IC11") (pin "21") (pinfunction "P21_21") (pintype "bidirectional"))
      (node (ref "IC7") (pin "3") (pinfunction "A_3") (pintype "bidirectional"))
    )
    (net (code "56") (name "C_PB3") (class "Default")
      (node (ref "IC11") (pin "17") (pinfunction "P17_17") (pintype "bidirectional"))
      (node (ref "IC8") (pin "3") (pinfunction "A_3") (pintype "bidirectional"))
    )
    (net (code "57") (name "C_PB4") (class "Default")
      (node (ref "IC10") (pin "3") (pinfunction "A_3") (pintype "bidirectional"))
      (node (ref "IC11") (pin "12") (pinfunction "P12_12") (pintype "bidirectional"))
    )
    (net (code "58") (name "C_PB5") (class "Default")
      (node (ref "IC11") (pin "7") (pinfunction "P7_7") (pintype "bidirectional"))
      (node (ref "IC12") (pin "3") (pinfunction "A_3") (pintype "bidirectional"))
    )
    (net (code "59") (name "C_PB6") (class "Default")
      (node (ref "IC11") (pin "5") (pinfunction "P5_5") (pintype "bidirectional"))
      (node (ref "IC13") (pin "3") (pinfunction "A_3") (pintype "bidirectional"))
    )
    (net (code "60") (name "C_PB7") (class "Default")
      (node (ref "IC11") (pin "1") (pinfunction "P1_1") (pintype "bidirectional"))
      (node (ref "IC14") (pin "3") (pinfunction "A_3") (pintype "bidirectional"))
    )
    (net (code "61") (name "D1_XIN") (class "Default")
      (node (ref "C5") (pin "1") (pinfunction "1_1") (pintype "passive"))
      (node (ref "C70") (pin "2") (pinfunction "2_2") (pintype "passive"))
      (node (ref "IC9") (pin "6") (pinfunction "XIN_6") (pintype "bidirectional"))
      (node (ref "Q50") (pin "3") (pinfunction "2_3") (pintype "passive"))
    )
    (net (code "62") (name "D_A8") (class "Default")
      (node (ref "IC11") (pin "49") (pinfunction "P49_49") (pintype "bidirectional"))
      (node (ref "IC20") (pin "11") (pinfunction "PB08/SERCOM4_0_11") (pintype "bidirectional"))
      (node (ref "IC24") (pin "2") (pinfunction "1D_2") (pintype "input"))
      (node (ref "IC9") (pin "36") (pinfunction "PA0/A8_36") (pintype "bidirectional"))
    )
    (net (code "63") (name "D_A9") (class "Default")
      (node (ref "IC11") (pin "50") (pinfunction "P50_50") (pintype "bidirectional"))
      (node (ref "IC20") (pin "12") (pinfunction "PB09/SERCOM4_1_12") (pintype "bidirectional"))
      (node (ref "IC24") (pin "3") (pinfunction "2D_3") (pintype "input"))
      (node (ref "IC9") (pin "35") (pinfunction "PA1/A9_35") (pintype "bidirectional"))
    )
    (net (code "64") (name "D_A10") (class "Default")
      (node (ref "IC11") (pin "37") (pinfunction "P37_37") (pintype "bidirectional"))
      (node (ref "IC20") (pin "23") (pinfunction "PB10/SERCOM4_2_23") (pintype "bidirectional"))
      (node (ref "IC24") (pin "4") (pinfunction "3D_4") (pintype "input"))
      (node (ref "IC9") (pin "34") (pinfunction "PA2/A10_34") (pintype "bidirectional"))
    )
    (net (code "65") (name "D_A11") (class "Default")
      (node (ref "IC11") (pin "36") (pinfunction "P36_36") (pintype "bidirectional"))
      (node (ref "IC20") (pin "24") (pinfunction "PB11/SERCOM4_3_24") (pintype "bidirectional"))
      (node (ref "IC24") (pin "5") (pinfunction "4D_5") (pintype "input"))
      (node (ref "IC9") (pin "33") (pinfunction "PA3/A11_33") (pintype "bidirectional"))
    )
    (net (code "66") (name "D_A12") (class "Default")
      (node (ref "IC11") (pin "45") (pinfunction "P45_45") (pintype "bidirectional"))
      (node (ref "IC20") (pin "25") (pinfunction "PB12/SERCOM4_0_25") (pintype "bidirectional"))
      (node (ref "IC24") (pin "6") (pinfunction "5D_6") (pintype "input"))
      (node (ref "IC9") (pin "31") (pinfunction "PA4/A12_31") (pintype "bidirectional"))
    )
    (net (code "67") (name "D_A13") (class "Default")
      (node (ref "IC11") (pin "46") (pinfunction "P46_46") (pintype "bidirectional"))
      (node (ref "IC20") (pin "26") (pinfunction "PB13/SERCOM4_1_26") (pintype "bidirectional"))
      (node (ref "IC24") (pin "7") (pinfunction "6D_7") (pintype "input"))
      (node (ref "IC9") (pin "30") (pinfunction "PA5/A13_30") (pintype "bidirectional"))
    )
    (net (code "68") (name "D_A14") (class "Default")
      (node (ref "IC11") (pin "47") (pinfunction "P47_47") (pintype "bidirectional"))
      (node (ref "IC20") (pin "27") (pinfunction "PB14/SERCOM4_2_27") (pintype "bidirectional"))
      (node (ref "IC24") (pin "8") (pinfunction "7D_8") (pintype "input"))
      (node (ref "IC9") (pin "29") (pinfunction "PA6/A14_29") (pintype "bidirectional"))
    )
    (net (code "69") (name "D_A15") (class "Default")
      (node (ref "IC11") (pin "48") (pinfunction "P48_48") (pintype "bidirectional"))
      (node (ref "IC20") (pin "28") (pinfunction "PB15/SERCOM4_3_28") (pintype "bidirectional"))
      (node (ref "IC24") (pin "9") (pinfunction "8D_9") (pintype "input"))
      (node (ref "IC9") (pin "28") (pinfunction "PA7/A15_28") (pintype "bidirectional"))
    )
    (net (code "70") (name "D_ADR") (class "Default")
      (node (ref "IC11") (pin "90") (pinfunction "P90/GCLK0_90") (pintype "input"))
      (node (ref "IC9") (pin "9") (pinfunction "ADR_9") (pintype "output"))
      (node (ref "U1") (pin "9") (pinfunction "ADR_9") (pintype "bidirectional"))
    )
    (net (code "71") (name "D_AL0") (class "Default")
      (node (ref "IC11") (pin "64") (pinfunction "P64_64") (pintype "bidirectional"))
    )
    (net (code "72") (name "D_AL1") (class "Default")
      (node (ref "IC11") (pin "63") (pinfunction "P63_63") (pintype "bidirectional"))
    )
    (net (code "73") (name "D_AL2") (class "Default")
      (node (ref "IC11") (pin "44") (pinfunction "P44_44") (pintype "bidirectional"))
    )
    (net (code "74") (name "D_AL3") (class "Default")
      (node (ref "IC11") (pin "42") (pinfunction "P42_42") (pintype "bidirectional"))
    )
    (net (code "75") (name "D_AL4") (class "Default")
      (node (ref "IC11") (pin "79") (pinfunction "P79_79") (pintype "bidirectional"))
    )
    (net (code "76") (name "D_AL5") (class "Default")
      (node (ref "IC11") (pin "80") (pinfunction "P80_80") (pintype "bidirectional"))
    )
    (net (code "77") (name "D_AL6") (class "Default")
      (node (ref "IC11") (pin "57") (pinfunction "P57_57") (pintype "bidirectional"))
    )
    (net (code "78") (name "D_AL7") (class "Default")
      (node (ref "IC11") (pin "56") (pinfunction "P56_56") (pintype "bidirectional"))
    )
    (net (code "79") (name "D_ASR0") (class "Default")
      (node (ref "IC9") (pin "2") (pinfunction "ASR0_2") (pintype "input"))
      (node (ref "U1") (pin "2") (pinfunction "ASR0_2") (pintype "bidirectional"))
    )
    (net (code "80") (name "D_ASR1") (class "Default")
      (node (ref "IC9") (pin "1") (pinfunction "ASR1_1") (pintype "input"))
      (node (ref "U1") (pin "1") (pinfunction "ASR1_1") (pintype "bidirectional"))
    )
    (net (code "81") (name "D_ASR2") (class "Default")
      (node (ref "IC9") (pin "63") (pinfunction "ASR2_63") (pintype "input"))
      (node (ref "R2") (pin "4") (pinfunction "1_4") (pintype "passive"))
      (node (ref "U1") (pin "63") (pinfunction "ASR2_63") (pintype "bidirectional"))
    )
    (net (code "82") (name "D_ASR3") (class "Default")
      (node (ref "IC9") (pin "62") (pinfunction "ASR3_62") (pintype "input"))
      (node (ref "U1") (pin "62") (pinfunction "ASR3_62") (pintype "bidirectional"))
    )
    (net (code "83") (name "D_CCLK") (class "Default")
      (node (ref "IC11") (pin "87") (pinfunction "P87/GCLK3_87") (pintype "input"))
      (node (ref "IC9") (pin "8") (pinfunction "CCLK_8") (pintype "output"))
      (node (ref "U1") (pin "8") (pinfunction "DCLK_8") (pintype "bidirectional"))
    )
    (net (code "84") (name "D_DA0") (class "Default")
      (node (ref "IC11") (pin "75") (pinfunction "P75_75") (pintype "bidirectional"))
      (node (ref "IC20") (pin "61") (pinfunction "PB00/SERCOM5_2_61") (pintype "bidirectional"))
      (node (ref "IC22") (pin "2") (pinfunction "1D_2") (pintype "input"))
      (node (ref "IC23") (pin "18") (pinfunction "B1_18") (pintype "bidirectional"))
      (node (ref "IC9") (pin "27") (pinfunction "PB0/DA0_27") (pintype "bidirectional"))
    )
    (net (code "85") (name "D_DA1") (class "Default")
      (node (ref "IC11") (pin "76") (pinfunction "P76_76") (pintype "bidirectional"))
      (node (ref "IC20") (pin "62") (pinfunction "PB01/SERCOM5_3_62") (pintype "bidirectional"))
      (node (ref "IC22") (pin "3") (pinfunction "2D_3") (pintype "input"))
      (node (ref "IC23") (pin "17") (pinfunction "B2_17") (pintype "bidirectional"))
      (node (ref "IC9") (pin "26") (pinfunction "PB1/DA1_26") (pintype "bidirectional"))
    )
    (net (code "86") (name "D_DA2") (class "Default")
      (node (ref "IC11") (pin "77") (pinfunction "P77_77") (pintype "bidirectional"))
      (node (ref "IC20") (pin "63") (pinfunction "PB02/SERCOM5_0_63") (pintype "bidirectional"))
      (node (ref "IC22") (pin "4") (pinfunction "3D_4") (pintype "input"))
      (node (ref "IC23") (pin "16") (pinfunction "B3_16") (pintype "bidirectional"))
      (node (ref "IC9") (pin "25") (pinfunction "PB2/DA2_25") (pintype "bidirectional"))
    )
    (net (code "87") (name "D_DA3") (class "Default")
      (node (ref "IC11") (pin "60") (pinfunction "P60_60") (pintype "bidirectional"))
      (node (ref "IC20") (pin "64") (pinfunction "PB03/SERCOM5_1_64") (pintype "bidirectional"))
      (node (ref "IC22") (pin "5") (pinfunction "4D_5") (pintype "input"))
      (node (ref "IC23") (pin "15") (pinfunction "B4_15") (pintype "bidirectional"))
      (node (ref "IC9") (pin "24") (pinfunction "PB3/DA3_24") (pintype "bidirectional"))
    )
    (net (code "88") (name "D_DA4") (class "Default")
      (node (ref "IC11") (pin "72") (pinfunction "P72_72") (pintype "bidirectional"))
      (node (ref "IC20") (pin "5") (pinfunction "PB04_5") (pintype "bidirectional"))
      (node (ref "IC22") (pin "6") (pinfunction "5D_6") (pintype "input"))
      (node (ref "IC23") (pin "14") (pinfunction "B5_14") (pintype "bidirectional"))
      (node (ref "IC9") (pin "23") (pinfunction "PB4/DA4_23") (pintype "bidirectional"))
    )
    (net (code "89") (name "D_DA5") (class "Default")
      (node (ref "IC11") (pin "71") (pinfunction "P71_71") (pintype "bidirectional"))
      (node (ref "IC20") (pin "6") (pinfunction "PB05_6") (pintype "bidirectional"))
      (node (ref "IC22") (pin "7") (pinfunction "6D_7") (pintype "input"))
      (node (ref "IC23") (pin "13") (pinfunction "B6_13") (pintype "bidirectional"))
      (node (ref "IC9") (pin "22") (pinfunction "PB5/DA5_22") (pintype "bidirectional"))
    )
    (net (code "90") (name "D_DA6") (class "Default")
      (node (ref "IC11") (pin "61") (pinfunction "P61_61") (pintype "bidirectional"))
      (node (ref "IC20") (pin "9") (pinfunction "PB06_9") (pintype "bidirectional"))
      (node (ref "IC22") (pin "8") (pinfunction "7D_8") (pintype "input"))
      (node (ref "IC23") (pin "12") (pinfunction "B7_12") (pintype "bidirectional"))
      (node (ref "IC9") (pin "21") (pinfunction "PB6/DA6_21") (pintype "bidirectional"))
    )
    (net (code "91") (name "D_DA7") (class "Default")
      (node (ref "IC11") (pin "58") (pinfunction "P58_58") (pintype "bidirectional"))
      (node (ref "IC20") (pin "10") (pinfunction "PB07_10") (pintype "bidirectional"))
      (node (ref "IC22") (pin "9") (pinfunction "8D_9") (pintype "input"))
      (node (ref "IC23") (pin "11") (pinfunction "B8_11") (pintype "bidirectional"))
      (node (ref "IC9") (pin "20") (pinfunction "PB7/DA7_20") (pintype "bidirectional"))
    )
    (net (code "92") (name "D_DOUT0") (class "Default")
      (node (ref "IC9") (pin "61") (pinfunction "DOUT0_61") (pintype "bidirectional"))
      (node (ref "U1") (pin "61") (pinfunction "DOUT0_61") (pintype "bidirectional"))
    )
    (net (code "93") (name "D_DOUT1") (class "Default")
      (node (ref "IC9") (pin "60") (pinfunction "DOUT1_60") (pintype "bidirectional"))
      (node (ref "U1") (pin "60") (pinfunction "DOUT1_60") (pintype "bidirectional"))
    )
    (net (code "94") (name "D_DOUT2") (class "Default")
      (node (ref "IC9") (pin "59") (pinfunction "DOUT2_59") (pintype "bidirectional"))
      (node (ref "U1") (pin "59") (pinfunction "DOUT2_59") (pintype "bidirectional"))
    )
    (net (code "95") (name "D_DOUT3") (class "Default")
      (node (ref "IC9") (pin "58") (pinfunction "DOUT3_58") (pintype "bidirectional"))
      (node (ref "U1") (pin "58") (pinfunction "DOUT3_58") (pintype "bidirectional"))
    )
    (net (code "96") (name "D_DOUT4") (class "Default")
      (node (ref "IC9") (pin "57") (pinfunction "DOUT4_57") (pintype "bidirectional"))
      (node (ref "U1") (pin "57") (pinfunction "DOUT4_57") (pintype "bidirectional"))
    )
    (net (code "97") (name "D_DOUT5") (class "Default")
      (node (ref "IC9") (pin "56") (pinfunction "DOUT5_56") (pintype "bidirectional"))
      (node (ref "U1") (pin "56") (pinfunction "DOUT5_56") (pintype "bidirectional"))
    )
    (net (code "98") (name "D_DOUT6") (class "Default")
      (node (ref "IC9") (pin "55") (pinfunction "DOUT6_55") (pintype "bidirectional"))
      (node (ref "U1") (pin "55") (pinfunction "DOUT6_55") (pintype "bidirectional"))
    )
    (net (code "99") (name "D_DOUT7") (class "Default")
      (node (ref "IC9") (pin "54") (pinfunction "DOUT7_54") (pintype "bidirectional"))
      (node (ref "U1") (pin "54") (pinfunction "DOUT7_54") (pintype "bidirectional"))
    )
    (net (code "100") (name "D_PA0") (class "Default")
      (node (ref "IC4") (pin "4") (pinfunction "B_4") (pintype "bidirectional"))
      (node (ref "U1") (pin "36") (pinfunction "PA0_36") (pintype "bidirectional"))
    )
    (net (code "101") (name "D_PA1") (class "Default")
      (node (ref "IC3") (pin "4") (pinfunction "B_4") (pintype "bidirectional"))
      (node (ref "U1") (pin "35") (pinfunction "PA1_35") (pintype "bidirectional"))
    )
    (net (code "102") (name "D_PA2") (class "Default")
      (node (ref "IC2") (pin "4") (pinfunction "B_4") (pintype "bidirectional"))
      (node (ref "U1") (pin "34") (pinfunction "PA2_34") (pintype "bidirectional"))
    )
    (net (code "103") (name "D_PA3") (class "Default")
      (node (ref "IC1") (pin "4") (pinfunction "B_4") (pintype "bidirectional"))
      (node (ref "U1") (pin "33") (pinfunction "PA3_33") (pintype "bidirectional"))
    )
    (net (code "104") (name "D_PA4") (class "Default")
      (node (ref "IC16") (pin "4") (pinfunction "B_4") (pintype "bidirectional"))
      (node (ref "U1") (pin "31") (pinfunction "PA4_31") (pintype "bidirectional"))
    )
    (net (code "105") (name "D_PA5") (class "Default")
      (node (ref "IC17") (pin "4") (pinfunction "B_4") (pintype "bidirectional"))
      (node (ref "U1") (pin "30") (pinfunction "PA5_30") (pintype "bidirectional"))
    )
    (net (code "106") (name "D_PA6") (class "Default")
      (node (ref "IC18") (pin "4") (pinfunction "B_4") (pintype "bidirectional"))
      (node (ref "U1") (pin "29") (pinfunction "PA6_29") (pintype "bidirectional"))
    )
    (net (code "107") (name "D_PA7") (class "Default")
      (node (ref "IC19") (pin "4") (pinfunction "B_4") (pintype "bidirectional"))
      (node (ref "U1") (pin "28") (pinfunction "PA7_28") (pintype "bidirectional"))
    )
    (net (code "108") (name "D_PB0") (class "Default")
      (node (ref "IC5") (pin "4") (pinfunction "B_4") (pintype "bidirectional"))
      (node (ref "U1") (pin "27") (pinfunction "PB0_27") (pintype "bidirectional"))
    )
    (net (code "109") (name "D_PB1") (class "Default")
      (node (ref "IC6") (pin "4") (pinfunction "B_4") (pintype "bidirectional"))
      (node (ref "U1") (pin "26") (pinfunction "PB1_26") (pintype "bidirectional"))
    )
    (net (code "110") (name "D_PB2") (class "Default")
      (node (ref "IC7") (pin "4") (pinfunction "B_4") (pintype "bidirectional"))
      (node (ref "U1") (pin "25") (pinfunction "PB2_25") (pintype "bidirectional"))
    )
    (net (code "111") (name "D_PB3") (class "Default")
      (node (ref "IC8") (pin "4") (pinfunction "B_4") (pintype "bidirectional"))
      (node (ref "U1") (pin "24") (pinfunction "PB3_24") (pintype "bidirectional"))
    )
    (net (code "112") (name "D_PB4") (class "Default")
      (node (ref "IC10") (pin "4") (pinfunction "B_4") (pintype "bidirectional"))
      (node (ref "U1") (pin "23") (pinfunction "PB4_23") (pintype "bidirectional"))
    )
    (net (code "113") (name "D_PB5") (class "Default")
      (node (ref "IC12") (pin "4") (pinfunction "B_4") (pintype "bidirectional"))
      (node (ref "U1") (pin "22") (pinfunction "PB5_22") (pintype "bidirectional"))
    )
    (net (code "114") (name "D_PB6") (class "Default")
      (node (ref "IC13") (pin "4") (pinfunction "B_4") (pintype "bidirectional"))
      (node (ref "U1") (pin "21") (pinfunction "PB6_21") (pintype "bidirectional"))
    )
    (net (code "115") (name "D_PB7") (class "Default")
      (node (ref "IC14") (pin "4") (pinfunction "B_4") (pintype "bidirectional"))
      (node (ref "U1") (pin "20") (pinfunction "PB7_20") (pintype "bidirectional"))
    )
    (net (code "116") (name "D_PC0") (class "Default")
      (node (ref "IC9") (pin "48") (pinfunction "PC0_48") (pintype "bidirectional"))
      (node (ref "U1") (pin "48") (pinfunction "PC0_48") (pintype "bidirectional"))
    )
    (net (code "117") (name "D_PC1") (class "Default")
      (node (ref "IC9") (pin "47") (pinfunction "PC1_47") (pintype "bidirectional"))
      (node (ref "U1") (pin "47") (pinfunction "PC1_47") (pintype "bidirectional"))
    )
    (net (code "118") (name "D_PC2") (class "Default")
      (node (ref "IC9") (pin "46") (pinfunction "PC2_46") (pintype "bidirectional"))
      (node (ref "U1") (pin "46") (pinfunction "PC2_46") (pintype "bidirectional"))
    )
    (net (code "119") (name "D_PC3{slash}SDAT0") (class "Default")
      (node (ref "IC9") (pin "45") (pinfunction "PC3_45") (pintype "bidirectional"))
      (node (ref "R2") (pin "1") (pinfunction "1_1") (pintype "passive"))
      (node (ref "U1") (pin "45") (pinfunction "PC3_45") (pintype "bidirectional"))
    )
    (net (code "120") (name "D_PC4{slash}SCLK") (class "Default")
      (node (ref "IC9") (pin "44") (pinfunction "PC4_44") (pintype "bidirectional"))
      (node (ref "R2") (pin "2") (pinfunction "1_2") (pintype "passive"))
      (node (ref "U1") (pin "44") (pinfunction "PC4_44") (pintype "bidirectional"))
    )
    (net (code "121") (name "D_PC5{slash}SDAT1") (class "Default")
      (node (ref "IC9") (pin "43") (pinfunction "PC5_43") (pintype "bidirectional"))
      (node (ref "R2") (pin "3") (pinfunction "1_3") (pintype "passive"))
      (node (ref "U1") (pin "43") (pinfunction "PC5_43") (pintype "bidirectional"))
    )
    (net (code "122") (name "D_PC6") (class "Default")
      (node (ref "IC9") (pin "42") (pinfunction "PC6_42") (pintype "bidirectional"))
      (node (ref "U1") (pin "42") (pinfunction "PC6_42") (pintype "bidirectional"))
    )
    (net (code "123") (name "D_PC7") (class "Default")
      (node (ref "IC9") (pin "41") (pinfunction "PC7_41") (pintype "bidirectional"))
      (node (ref "U1") (pin "41") (pinfunction "PC7_41") (pintype "bidirectional"))
    )
    (net (code "124") (name "D_PD0") (class "Default")
      (node (ref "IC9") (pin "40") (pinfunction "PD0_40") (pintype "bidirectional"))
      (node (ref "U1") (pin "40") (pinfunction "PD0_40") (pintype "bidirectional"))
    )
    (net (code "125") (name "D_PD1") (class "Default")
      (node (ref "IC9") (pin "39") (pinfunction "PD1_39") (pintype "bidirectional"))
      (node (ref "U1") (pin "39") (pinfunction "PD1_39") (pintype "bidirectional"))
    )
    (net (code "126") (name "D_PD2") (class "Default")
      (node (ref "IC9") (pin "38") (pinfunction "PD2_38") (pintype "bidirectional"))
      (node (ref "U1") (pin "38") (pinfunction "PD2_38") (pintype "bidirectional"))
    )
    (net (code "127") (name "D_PD3") (class "Default")
      (node (ref "IC9") (pin "37") (pinfunction "PD3_37") (pintype "bidirectional"))
      (node (ref "U1") (pin "37") (pinfunction "PD3_37") (pintype "bidirectional"))
    )
    (net (code "128") (name "D_SCLK") (class "Default")
      (node (ref "IC9") (pin "13") (pinfunction "CLK_13") (pintype "output"))
      (node (ref "R3") (pin "2") (pinfunction "1_2") (pintype "passive"))
      (node (ref "U1") (pin "13") (pinfunction "CLK_13") (pintype "bidirectional"))
    )
    (net (code "129") (name "D_SCLKB") (class "Default")
      (node (ref "IC20") (pin "18") (pinfunction "PA09/SERCOM0_1/SERCOM2_1_18") (pintype "bidirectional"))
      (node (ref "IC20") (pin "36") (pinfunction "PA17/SERCOM1_1/SERCOM3_1_36") (pintype "bidirectional"))
      (node (ref "R2") (pin "7") (pinfunction "2_7") (pintype "passive"))
    )
    (net (code "130") (name "D_SIN0") (class "Default")
      (node (ref "IC9") (pin "17") (pinfunction "SIN0_17") (pintype "input"))
      (node (ref "R3") (pin "1") (pinfunction "1_1") (pintype "passive"))
      (node (ref "U1") (pin "17") (pinfunction "SIN0_17") (pintype "bidirectional"))
    )
    (net (code "131") (name "D_SIN1") (class "Default")
      (node (ref "IC9") (pin "16") (pinfunction "SIN1_16") (pintype "input"))
      (node (ref "U1") (pin "16") (pinfunction "SIN1_16") (pintype "bidirectional"))
    )
    (net (code "132") (name "D_SIN2") (class "Default")
      (node (ref "IC9") (pin "15") (pinfunction "SIN2_15") (pintype "input"))
      (node (ref "U1") (pin "15") (pinfunction "SIN2_15") (pintype "bidirectional"))
    )
    (net (code "133") (name "D_SIN3") (class "Default")
      (node (ref "IC9") (pin "14") (pinfunction "SIN3_14") (pintype "input"))
      (node (ref "U1") (pin "14") (pinfunction "SIN3_14") (pintype "bidirectional"))
    )
    (net (code "134") (name "D_SOUT0") (class "Default")
      (node (ref "IC9") (pin "19") (pinfunction "SOUT0_19") (pintype "output"))
      (node (ref "R3") (pin "3") (pinfunction "1_3") (pintype "passive"))
      (node (ref "U1") (pin "19") (pinfunction "SOUT0_19") (pintype "bidirectional"))
    )
    (net (code "135") (name "D_SOUT1") (class "Default")
      (node (ref "IC9") (pin "18") (pinfunction "SOUT1_18") (pintype "output"))
      (node (ref "U1") (pin "18") (pinfunction "SOUT1_18") (pintype "bidirectional"))
    )
    (net (code "136") (name "GND") (class "Default")
      (node (ref "C1") (pin "1") (pinfunction "1_1") (pintype "passive"))
      (node (ref "C2") (pin "1") (pinfunction "1_1") (pintype "passive"))
      (node (ref "C3") (pin "2") (pinfunction "2_2") (pintype "passive"))
      (node (ref "C4") (pin "2") (pinfunction "2_2") (pintype "passive"))
      (node (ref "C50") (pin "2") (pinfunction "2_2") (pintype "passive"))
      (node (ref "C51") (pin "1") (pinfunction "1_1") (pintype "passive"))
      (node (ref "C52") (pin "1") (pinfunction "1_1") (pintype "passive"))
      (node (ref "C53") (pin "1") (pinfunction "1_1") (pintype "passive"))
      (node (ref "C54") (pin "2") (pinfunction "2_2") (pintype "passive"))
      (node (ref "C55") (pin "2") (pinfunction "2_2") (pintype "passive"))
      (node (ref "C56") (pin "2") (pinfunction "2_2") (pintype "passive"))
      (node (ref "C57") (pin "2") (pinfunction "2_2") (pintype "passive"))
      (node (ref "C58") (pin "2") (pinfunction "2_2") (pintype "passive"))
      (node (ref "C59") (pin "2") (pinfunction "2_2") (pintype "passive"))
      (node (ref "C60") (pin "1") (pinfunction "1_1") (pintype "passive"))
      (node (ref "C61") (pin "1") (pinfunction "1_1") (pintype "passive"))
      (node (ref "C62") (pin "1") (pinfunction "1_1") (pintype "passive"))
      (node (ref "C63") (pin "1") (pinfunction "1_1") (pintype "passive"))
      (node (ref "C64") (pin "1") (pinfunction "1_1") (pintype "passive"))
      (node (ref "C65") (pin "1") (pinfunction "1_1") (pintype "passive"))
      (node (ref "C66") (pin "1") (pinfunction "1_1") (pintype "passive"))
      (node (ref "C67") (pin "1") (pinfunction "1_1") (pintype "passive"))
      (node (ref "C68") (pin "1") (pinfunction "1_1") (pintype "passive"))
      (node (ref "C69") (pin "2") (pinfunction "2_2") (pintype "passive"))
      (node (ref "C70") (pin "1") (pinfunction "1_1") (pintype "passive"))
      (node (ref "C71") (pin "1") (pinfunction "1_1") (pintype "passive"))
      (node (ref "C72") (pin "1") (pinfunction "1_1") (pintype "passive"))
      (node (ref "C73") (pin "1") (pinfunction "1_1") (pintype "passive"))
      (node (ref "C74") (pin "1") (pinfunction "1_1") (pintype "passive"))
      (node (ref "C75") (pin "1") (pinfunction "1_1") (pintype "passive"))
      (node (ref "C76") (pin "1") (pinfunction "1_1") (pintype "passive"))
      (node (ref "C77") (pin "1") (pinfunction "1_1") (pintype "passive"))
      (node (ref "C78") (pin "1") (pinfunction "1_1") (pintype "passive"))
      (node (ref "C79") (pin "1") (pinfunction "1_1") (pintype "passive"))
      (node (ref "C80") (pin "1") (pinfunction "1_1") (pintype "passive"))
      (node (ref "C81") (pin "1") (pinfunction "1_1") (pintype "passive"))
      (node (ref "IC1") (pin "2") (pinfunction "GND_2") (pintype "power_in"))
      (node (ref "IC10") (pin "2") (pinfunction "GND_2") (pintype "power_in"))
      (node (ref "IC11") (pin "11") (pinfunction "PORTEN_11") (pintype "bidirectional"))
      (node (ref "IC11") (pin "26") (pinfunction "GND_26") (pintype "power_in"))
      (node (ref "IC11") (pin "38") (pinfunction "GND_38") (pintype "power_in"))
      (node (ref "IC11") (pin "43") (pinfunction "GND_43") (pintype "power_in"))
      (node (ref "IC11") (pin "59") (pinfunction "GND_59") (pintype "power_in"))
      (node (ref "IC11") (pin "74") (pinfunction "GND_74") (pintype "power_in"))
      (node (ref "IC11") (pin "86") (pinfunction "GND_86") (pintype "power_in"))
      (node (ref "IC11") (pin "95") (pinfunction "GND_95") (pintype "power_in"))
      (node (ref "IC12") (pin "2") (pinfunction "GND_2") (pintype "power_in"))
      (node (ref "IC13") (pin "2") (pinfunction "GND_2") (pintype "power_in"))
      (node (ref "IC14") (pin "2") (pinfunction "GND_2") (pintype "power_in"))
      (node (ref "IC15") (pin "2") (pinfunction "GND_2") (pintype "power_in"))
      (node (ref "IC16") (pin "2") (pinfunction "GND_2") (pintype "power_in"))
      (node (ref "IC17") (pin "2") (pinfunction "GND_2") (pintype "power_in"))
      (node (ref "IC18") (pin "2") (pinfunction "GND_2") (pintype "power_in"))
      (node (ref "IC19") (pin "2") (pinfunction "GND_2") (pintype "power_in"))
      (node (ref "IC2") (pin "2") (pinfunction "GND_2") (pintype "power_in"))
      (node (ref "IC20") (pin "22") (pinfunction "GND_22") (pintype "power_in"))
      (node (ref "IC20") (pin "33") (pinfunction "GND_33") (pintype "power_in"))
      (node (ref "IC20") (pin "47") (pinfunction "GND_47") (pintype "power_in"))
      (node (ref "IC20") (pin "54") (pinfunction "GNDCORE_54") (pintype "power_in"))
      (node (ref "IC20") (pin "7") (pinfunction "GNDANA_7") (pintype "power_in"))
      (node (ref "IC21") (pin "14") (pinfunction "GND_14") (pintype "power_in"))
      (node (ref "IC3") (pin "2") (pinfunction "GND_2") (pintype "power_in"))
      (node (ref "IC4") (pin "2") (pinfunction "GND_2") (pintype "power_in"))
      (node (ref "IC5") (pin "2") (pinfunction "GND_2") (pintype "power_in"))
      (node (ref "IC6") (pin "2") (pinfunction "GND_2") (pintype "power_in"))
      (node (ref "IC7") (pin "2") (pinfunction "GND_2") (pintype "power_in"))
      (node (ref "IC8") (pin "2") (pinfunction "GND_2") (pintype "power_in"))
      (node (ref "IC9") (pin "12") (pinfunction "I/~{E}_12") (pintype "input"))
      (node (ref "IC9") (pin "32") (pinfunction "GND_32") (pintype "power_in"))
      (node (ref "JP1") (pin "GND") (pinfunction "5_GND") (pintype "passive"))
      (node (ref "U1") (pin "32") (pinfunction "GND_32") (pintype "bidirectional"))
      (node (ref "X1") (pin "3") (pinfunction "B_3") (pintype "passive"))
      (node (ref "X1") (pin "5") (pinfunction "B_5") (pintype "passive"))
      (node (ref "X1") (pin "9") (pinfunction "B_9") (pintype "passive"))
      (node (ref "X2") (pin "6") (pinfunction "6_6") (pintype "passive"))
    )
    (net (code "137") (name "IO_1") (class "Default")
      (node (ref "IC11") (pin "70") (pinfunction "P70_70") (pintype "bidirectional"))
      (node (ref "IC20") (pin "29") (pinfunction "PA12/SERCOM2_0/SERCOM4_0_29") (pintype "bidirectional"))
    )
    (net (code "138") (name "IO_2") (class "Default")
      (node (ref "IC11") (pin "69") (pinfunction "P69_69") (pintype "bidirectional"))
      (node (ref "IC20") (pin "30") (pinfunction "PA13/SERCOM2_1/SERCOM4_1_30") (pintype "bidirectional"))
    )
    (net (code "139") (name "IO_3") (class "Default")
      (node (ref "IC11") (pin "68") (pinfunction "P68_68") (pintype "bidirectional"))
      (node (ref "IC20") (pin "31") (pinfunction "PA14/SERCOM2_2/SERCOM4_2/XIN_31") (pintype "bidirectional"))
    )
    (net (code "140") (name "IO_4") (class "Default")
      (node (ref "IC11") (pin "67") (pinfunction "P67_67") (pintype "bidirectional"))
      (node (ref "IC20") (pin "38") (pinfunction "PA19/SERCOM1_3/SERCOM3_3_38") (pintype "bidirectional"))
    )
    (net (code "141") (name "N$8") (class "Default")
      (node (ref "IC21") (pin "7") (pinfunction "A3_7") (pintype "input"))
    )
    (net (code "142") (name "N$9") (class "Default")
      (node (ref "IC21") (pin "6") (pinfunction "A4_6") (pintype "input"))
    )
    (net (code "143") (name "N$10") (class "Default")
      (node (ref "IC21") (pin "5") (pinfunction "A5_5") (pintype "input"))
    )
    (net (code "144") (name "N$11") (class "Default")
      (node (ref "IC21") (pin "4") (pinfunction "A6_4") (pintype "input"))
    )
    (net (code "145") (name "N$12") (class "Default")
      (node (ref "IC21") (pin "3") (pinfunction "A7_3") (pintype "input"))
    )
    (net (code "146") (name "Net-(IC9A-XOUT)") (class "Default")
      (node (ref "C69") (pin "1") (pinfunction "1_1") (pintype "passive"))
      (node (ref "IC9") (pin "7") (pinfunction "XOUT_7") (pintype "bidirectional"))
      (node (ref "Q50") (pin "1") (pinfunction "1_1") (pintype "passive"))
    )
    (net (code "147") (name "Net-(IC20-PA00{slash}SERCOM1_0{slash}XIN32)") (class "Default")
      (node (ref "C52") (pin "2") (pinfunction "2_2") (pintype "passive"))
      (node (ref "IC20") (pin "1") (pinfunction "PA00/SERCOM1_0/XIN32_1") (pintype "bidirectional"))
      (node (ref "X50") (pin "1") (pinfunction "1_1") (pintype "passive"))
    )
    (net (code "148") (name "Net-(IC20-PA01{slash}SERCOM1_1{slash}XOUT32)") (class "Default")
      (node (ref "C51") (pin "2") (pinfunction "2_2") (pintype "passive"))
      (node (ref "IC20") (pin "2") (pinfunction "PA01/SERCOM1_1/XOUT32_2") (pintype "bidirectional"))
      (node (ref "X50") (pin "2") (pinfunction "2_2") (pintype "passive"))
    )
    (net (code "149") (name "Net-(IC20-PA04{slash}SERCOM0_0)") (class "Default")
      (node (ref "IC20") (pin "13") (pinfunction "PA04/SERCOM0_0_13") (pintype "bidirectional"))
      (node (ref "R3") (pin "8") (pinfunction "2_8") (pintype "passive"))
    )
    (net (code "150") (name "Net-(IC20-PA05{slash}SERCOM0_1)") (class "Default")
      (node (ref "IC20") (pin "14") (pinfunction "PA05/SERCOM0_1_14") (pintype "bidirectional"))
      (node (ref "R3") (pin "7") (pinfunction "2_7") (pintype "passive"))
    )
    (net (code "151") (name "Net-(IC20-PA06{slash}SERCOM0_2)") (class "Default")
      (node (ref "IC20") (pin "15") (pinfunction "PA06/SERCOM0_2_15") (pintype "bidirectional"))
      (node (ref "R3") (pin "6") (pinfunction "2_6") (pintype "passive"))
    )
    (net (code "152") (name "Net-(IC20-PA08{slash}SERCOM0_0{slash}SERCOM2_0)") (class "Default")
      (node (ref "IC20") (pin "17") (pinfunction "PA08/SERCOM0_0/SERCOM2_0_17") (pintype "bidirectional"))
      (node (ref "IC20") (pin "35") (pinfunction "PA16/SERCOM1_0/SERCOM3_0\\_35") (pintype "bidirectional"))
      (node (ref "R2") (pin "8") (pinfunction "2_8") (pintype "passive"))
    )
    (net (code "153") (name "Net-(IC20-PA10{slash}SERCOM0_2{slash}SERCOM2_2)") (class "Default")
      (node (ref "IC20") (pin "19") (pinfunction "PA10/SERCOM0_2/SERCOM2_2_19") (pintype "bidirectional"))
      (node (ref "IC20") (pin "37") (pinfunction "PA18/SERCOM1_2/SERCOM3_2_37") (pintype "bidirectional"))
      (node (ref "R2") (pin "6") (pinfunction "2_6") (pintype "passive"))
    )
    (net (code "154") (name "Net-(IC20-PA11{slash}SERCOM0_3{slash}SERCOM2_3)") (class "Default")
      (node (ref "C5") (pin "2") (pinfunction "2_2") (pintype "passive"))
      (node (ref "IC20") (pin "20") (pinfunction "PA11/SERCOM0_3/SERCOM2_3_20") (pintype "bidirectional"))
    )
    (net (code "155") (name "Net-(IC20-PA21{slash}SERCOM5_3{slash}SERCOM3_3)") (class "Default")
      (node (ref "IC20") (pin "42") (pinfunction "PA21/SERCOM5_3/SERCOM3_3_42") (pintype "bidirectional"))
      (node (ref "R2") (pin "5") (pinfunction "2_5") (pintype "passive"))
    )
    (net (code "156") (name "Net-(IC20-PA22{slash}SERCOM3_0{slash}SERCOM5_0)") (class "Default")
      (node (ref "IC20") (pin "43") (pinfunction "PA22/SERCOM3_0/SERCOM5_0_43") (pintype "bidirectional"))
      (node (ref "R4") (pin "2") (pinfunction "1_2") (pintype "passive"))
    )
    (net (code "157") (name "Net-(IC20-PA23{slash}SERCOM3_1{slash}SERCOM5_1)") (class "Default")
      (node (ref "IC20") (pin "44") (pinfunction "PA23/SERCOM3_1/SERCOM5_1_44") (pintype "bidirectional"))
      (node (ref "R4") (pin "3") (pinfunction "1_3") (pintype "passive"))
    )
    (net (code "158") (name "Net-(IC20-PA24{slash}SERCOM3_2{slash}SERCOM5_2)") (class "Default")
      (node (ref "IC20") (pin "45") (pinfunction "PA24/SERCOM3_2/SERCOM5_2_45") (pintype "bidirectional"))
      (node (ref "R4") (pin "1") (pinfunction "1_1") (pintype "passive"))
    )
    (net (code "159") (name "Net-(IC20-PA25{slash}SERCOM3_3{slash}SERCOM5_3)") (class "Default")
      (node (ref "IC20") (pin "46") (pinfunction "PA25/SERCOM3_3/SERCOM5_3_46") (pintype "bidirectional"))
      (node (ref "R4") (pin "4") (pinfunction "1_4") (pintype "passive"))
    )
    (net (code "160") (name "Net-(IC20-PA27)") (class "Default")
      (node (ref "IC20") (pin "51") (pinfunction "PA27_51") (pintype "bidirectional"))
      (node (ref "TP6") (pin "TP") (pinfunction "TP_TP") (pintype "input"))
    )
    (net (code "161") (name "Net-(IC20-PA28)") (class "Default")
      (node (ref "IC20") (pin "53") (pinfunction "PA28_53") (pintype "bidirectional"))
      (node (ref "TP7") (pin "TP") (pinfunction "TP_TP") (pintype "input"))
    )
    (net (code "162") (name "Net-(IC20-VDDCORE)") (class "Default")
      (node (ref "C50") (pin "1") (pinfunction "1_1") (pintype "passive"))
      (node (ref "C54") (pin "1") (pinfunction "1_1") (pintype "passive"))
      (node (ref "IC20") (pin "55") (pinfunction "VDDCORE_55") (pintype "power_in"))
    )
    (net (code "163") (name "Net-(IC20-VDDIN)") (class "Default")
      (node (ref "C56") (pin "1") (pinfunction "1_1") (pintype "passive"))
      (node (ref "IC20") (pin "56") (pinfunction "VDDIN_56") (pintype "power_in"))
    )
    (net (code "164") (name "SWCLK") (class "Default")
      (node (ref "IC20") (pin "57") (pinfunction "PA30/SERCOM1_2/SWCLK_57") (pintype "bidirectional"))
      (node (ref "X1") (pin "4") (pinfunction "B_4") (pintype "passive"))
    )
    (net (code "165") (name "SWDIO") (class "Default")
      (node (ref "IC20") (pin "58") (pinfunction "PA31/SERCOM1_3/SWDIO_58") (pintype "bidirectional"))
      (node (ref "X1") (pin "2") (pinfunction "B_2") (pintype "passive"))
    )
    (net (code "166") (name "TCK") (class "Default")
      (node (ref "IC11") (pin "62") (pinfunction "TCK_62") (pintype "input"))
      (node (ref "IC20") (pin "49") (pinfunction "PB22/SERCOM5_2_49") (pintype "bidirectional"))
      (node (ref "JP1") (pin "TCK") (pinfunction "4_TCK") (pintype "passive"))
      (node (ref "TP4") (pin "TP") (pinfunction "TP_TP") (pintype "input"))
    )
    (net (code "167") (name "TDI") (class "Default")
      (node (ref "IC11") (pin "4") (pinfunction "TDI_4") (pintype "input"))
      (node (ref "IC20") (pin "3") (pinfunction "PA02_3") (pintype "bidirectional"))
      (node (ref "JP1") (pin "TDI") (pinfunction "2_TDI") (pintype "passive"))
      (node (ref "TP3") (pin "TP") (pinfunction "TP_TP") (pintype "input"))
    )
    (net (code "168") (name "TDO") (class "Default")
      (node (ref "IC11") (pin "73") (pinfunction "TDO_73") (pintype "output"))
      (node (ref "IC20") (pin "4") (pinfunction "PA03_4") (pintype "bidirectional"))
      (node (ref "JP1") (pin "TDO") (pinfunction "3_TDO") (pintype "passive"))
      (node (ref "TP2") (pin "TP") (pinfunction "TP_TP") (pintype "input"))
    )
    (net (code "169") (name "TMS") (class "Default")
      (node (ref "IC11") (pin "15") (pinfunction "TMS_15") (pintype "input"))
      (node (ref "IC20") (pin "50") (pinfunction "PB23/SERCOM5_3_50") (pintype "bidirectional"))
      (node (ref "JP1") (pin "TMS") (pinfunction "1_TMS") (pintype "passive"))
      (node (ref "R1") (pin "1") (pinfunction "1_1") (pintype "passive"))
      (node (ref "TP5") (pin "TP") (pinfunction "TP_TP") (pintype "input"))
    )
    (net (code "170") (name "VCC") (class "Default")
      (node (ref "C2") (pin "2") (pinfunction "2_2") (pintype "passive"))
      (node (ref "C4") (pin "1") (pinfunction "1_1") (pintype "passive"))
      (node (ref "C53") (pin "2") (pinfunction "2_2") (pintype "passive"))
      (node (ref "C55") (pin "1") (pinfunction "1_1") (pintype "passive"))
      (node (ref "C57") (pin "1") (pinfunction "1_1") (pintype "passive"))
      (node (ref "C58") (pin "1") (pinfunction "1_1") (pintype "passive"))
      (node (ref "C59") (pin "1") (pinfunction "1_1") (pintype "passive"))
      (node (ref "C60") (pin "2") (pinfunction "2_2") (pintype "passive"))
      (node (ref "C80") (pin "2") (pinfunction "2_2") (pintype "passive"))
      (node (ref "C81") (pin "2") (pinfunction "2_2") (pintype "passive"))
      (node (ref "IC1") (pin "6") (pinfunction "VCCB_6") (pintype "power_in"))
      (node (ref "IC10") (pin "6") (pinfunction "VCCB_6") (pintype "power_in"))
      (node (ref "IC12") (pin "6") (pinfunction "VCCB_6") (pintype "power_in"))
      (node (ref "IC13") (pin "6") (pinfunction "VCCB_6") (pintype "power_in"))
      (node (ref "IC14") (pin "6") (pinfunction "VCCB_6") (pintype "power_in"))
      (node (ref "IC15") (pin "1") (pinfunction "VIN_1") (pintype "power_in"))
      (node (ref "IC15") (pin "3") (pinfunction "EN_3") (pintype "input"))
      (node (ref "IC16") (pin "6") (pinfunction "VCCB_6") (pintype "power_in"))
      (node (ref "IC17") (pin "6") (pinfunction "VCCB_6") (pintype "power_in"))
      (node (ref "IC18") (pin "6") (pinfunction "VCCB_6") (pintype "power_in"))
      (node (ref "IC19") (pin "6") (pinfunction "VCCB_6") (pintype "power_in"))
      (node (ref "IC2") (pin "6") (pinfunction "VCCB_6") (pintype "power_in"))
      (node (ref "IC20") (pin "21") (pinfunction "VDDIO_21") (pintype "power_in"))
      (node (ref "IC20") (pin "34") (pinfunction "VDDIO_34") (pintype "power_in"))
      (node (ref "IC20") (pin "48") (pinfunction "VDDIO_48") (pintype "power_in"))
      (node (ref "IC20") (pin "8") (pinfunction "VDDANA_8") (pintype "power_in"))
      (node (ref "IC21") (pin "28") (pinfunction "VCC_28") (pintype "power_in"))
      (node (ref "IC3") (pin "6") (pinfunction "VCCB_6") (pintype "power_in"))
      (node (ref "IC4") (pin "6") (pinfunction "VCCB_6") (pintype "power_in"))
      (node (ref "IC5") (pin "6") (pinfunction "VCCB_6") (pintype "power_in"))
      (node (ref "IC6") (pin "6") (pinfunction "VCCB_6") (pintype "power_in"))
      (node (ref "IC7") (pin "6") (pinfunction "VCCB_6") (pintype "power_in"))
      (node (ref "IC8") (pin "6") (pinfunction "VCCB_6") (pintype "power_in"))
      (node (ref "IC9") (pin "64") (pinfunction "VCC_64") (pintype "power_in"))
      (node (ref "TP1") (pin "TP") (pinfunction "TP_TP") (pintype "input"))
      (node (ref "U1") (pin "64") (pinfunction "VCC_64") (pintype "bidirectional"))
      (node (ref "X1") (pin "1") (pinfunction "B_1") (pintype "passive"))
      (node (ref "X2") (pin "1") (pinfunction "1_1") (pintype "passive"))
    )
    (net (code "171") (name "VCC_CPLD") (class "Default")
      (node (ref "C1") (pin "2") (pinfunction "2_2") (pintype "passive"))
      (node (ref "C3") (pin "1") (pinfunction "1_1") (pintype "passive"))
      (node (ref "C61") (pin "2") (pinfunction "2_2") (pintype "passive"))
      (node (ref "C62") (pin "2") (pinfunction "2_2") (pintype "passive"))
      (node (ref "C63") (pin "2") (pinfunction "2_2") (pintype "passive"))
      (node (ref "C64") (pin "2") (pinfunction "2_2") (pintype "passive"))
      (node (ref "C65") (pin "2") (pinfunction "2_2") (pintype "passive"))
      (node (ref "C66") (pin "2") (pinfunction "2_2") (pintype "passive"))
      (node (ref "C67") (pin "2") (pinfunction "2_2") (pintype "passive"))
      (node (ref "C68") (pin "2") (pinfunction "2_2") (pintype "passive"))
      (node (ref "C71") (pin "2") (pinfunction "2_2") (pintype "passive"))
      (node (ref "C72") (pin "2") (pinfunction "2_2") (pintype "passive"))
      (node (ref "C73") (pin "2") (pinfunction "2_2") (pintype "passive"))
      (node (ref "C74") (pin "2") (pinfunction "2_2") (pintype "passive"))
      (node (ref "C75") (pin "2") (pinfunction "2_2") (pintype "passive"))
      (node (ref "C76") (pin "2") (pinfunction "2_2") (pintype "passive"))
      (node (ref "C77") (pin "2") (pinfunction "2_2") (pintype "passive"))
      (node (ref "C78") (pin "2") (pinfunction "2_2") (pintype "passive"))
      (node (ref "C79") (pin "2") (pinfunction "2_2") (pintype "passive"))
      (node (ref "IC1") (pin "1") (pinfunction "VCCA_1") (pintype "power_in"))
      (node (ref "IC10") (pin "1") (pinfunction "VCCA_1") (pintype "power_in"))
      (node (ref "IC11") (pin "18") (pinfunction "VCC_3V3_18") (pintype "power_in"))
      (node (ref "IC11") (pin "3") (pinfunction "VCC_3V3_3") (pintype "power_in"))
      (node (ref "IC11") (pin "34") (pinfunction "VCC_3V3_34") (pintype "power_in"))
      (node (ref "IC11") (pin "39") (pinfunction "VCC_3V3_39") (pintype "power_in"))
      (node (ref "IC11") (pin "51") (pinfunction "VCC_3V3_51") (pintype "power_in"))
      (node (ref "IC11") (pin "66") (pinfunction "VCC_3V3_66") (pintype "power_in"))
      (node (ref "IC11") (pin "82") (pinfunction "VCC_3V3_82") (pintype "power_in"))
      (node (ref "IC11") (pin "91") (pinfunction "VCC_3V3_91") (pintype "power_in"))
      (node (ref "IC12") (pin "1") (pinfunction "VCCA_1") (pintype "power_in"))
      (node (ref "IC13") (pin "1") (pinfunction "VCCA_1") (pintype "power_in"))
      (node (ref "IC14") (pin "1") (pinfunction "VCCA_1") (pintype "power_in"))
      (node (ref "IC15") (pin "5") (pinfunction "VOUT_5") (pintype "power_in"))
      (node (ref "IC16") (pin "1") (pinfunction "VCCA_1") (pintype "power_in"))
      (node (ref "IC17") (pin "1") (pinfunction "VCCA_1") (pintype "power_in"))
      (node (ref "IC18") (pin "1") (pinfunction "VCCA_1") (pintype "power_in"))
      (node (ref "IC19") (pin "1") (pinfunction "VCCA_1") (pintype "power_in"))
      (node (ref "IC2") (pin "1") (pinfunction "VCCA_1") (pintype "power_in"))
      (node (ref "IC3") (pin "1") (pinfunction "VCCA_1") (pintype "power_in"))
      (node (ref "IC4") (pin "1") (pinfunction "VCCA_1") (pintype "power_in"))
      (node (ref "IC5") (pin "1") (pinfunction "VCCA_1") (pintype "power_in"))
      (node (ref "IC6") (pin "1") (pinfunction "VCCA_1") (pintype "power_in"))
      (node (ref "IC7") (pin "1") (pinfunction "VCCA_1") (pintype "power_in"))
      (node (ref "IC8") (pin "1") (pinfunction "VCCA_1") (pintype "power_in"))
      (node (ref "JP1") (pin "VCC") (pinfunction "6_VCC") (pintype "passive"))
      (node (ref "R1") (pin "2") (pinfunction "2_2") (pintype "passive"))
    )
    (net (code "172") (name "X_ADR") (class "Default")
      (node (ref "IC11") (pin "53") (pinfunction "P53_53") (pintype "bidirectional"))
      (node (ref "IC20") (pin "59") (pinfunction "PB30/SERCOM5_0_59") (pintype "bidirectional"))
    )
    (net (code "173") (name "X_SCLK") (class "Default")
      (node (ref "R4") (pin "6") (pinfunction "2_6") (pintype "passive"))
      (node (ref "X2") (pin "3") (pinfunction "3_3") (pintype "passive"))
    )
    (net (code "174") (name "X_SRX") (class "Default")
      (node (ref "R4") (pin "8") (pinfunction "2_8") (pintype "passive"))
      (node (ref "X2") (pin "5") (pinfunction "5_5") (pintype "passive"))
    )
    (net (code "175") (name "X_STX") (class "Default")
      (node (ref "R4") (pin "7") (pinfunction "2_7") (pintype "passive"))
      (node (ref "X2") (pin "4") (pinfunction "4_4") (pintype "passive"))
    )
    (net (code "176") (name "unconnected-(IC20-PA15{slash}SERCOM2_3{slash}SERCOM4_3{slash}XOUT-Pad32)") (class "Default")
      (node (ref "IC20") (pin "32") (pinfunction "PA15/SERCOM2_3/SERCOM4_3/XOUT_32") (pintype "bidirectional"))
    )
    (net (code "177") (name "unconnected-(IC22A-C-Pad11)") (class "Default")
      (node (ref "IC22") (pin "11") (pinfunction "C_11") (pintype "input"))
    )
    (net (code "178") (name "unconnected-(IC22A-OC-Pad1)") (class "Default")
      (node (ref "IC22") (pin "1") (pinfunction "OC_1") (pintype "input"))
    )
    (net (code "179") (name "unconnected-(IC23A-DIR-Pad1)") (class "Default")
      (node (ref "IC23") (pin "1") (pinfunction "DIR_1") (pintype "input"))
    )
    (net (code "180") (name "unconnected-(IC23A-G-Pad19)") (class "Default")
      (node (ref "IC23") (pin "19") (pinfunction "G_19") (pintype "input"))
    )
    (net (code "181") (name "unconnected-(IC24A-C-Pad11)") (class "Default")
      (node (ref "IC24") (pin "11") (pinfunction "C_11") (pintype "input"))
    )
    (net (code "182") (name "unconnected-(IC24A-OC-Pad1)") (class "Default")
      (node (ref "IC24") (pin "1") (pinfunction "OC_1") (pintype "input"))
    )
    (net (code "183") (name "unconnected-(R3D-1-Pad4)") (class "Default")
      (node (ref "R3") (pin "4") (pinfunction "1_4") (pintype "passive"))
    )
    (net (code "184") (name "unconnected-(R3D-2-Pad5)") (class "Default")
      (node (ref "R3") (pin "5") (pinfunction "2_5") (pintype "passive"))
    )
    (net (code "185") (name "unconnected-(U1-I{slash}~{E}-Pad12)") (class "Default")
      (node (ref "U1") (pin "12") (pinfunction "I/~{E}_12") (pintype "bidirectional"))
    )
    (net (code "186") (name "unconnected-(U1-XIN-Pad6)") (class "Default")
      (node (ref "U1") (pin "6") (pinfunction "XIN_6") (pintype "bidirectional"))
    )
    (net (code "187") (name "unconnected-(U1-XOUT-Pad7)") (class "Default")
      (node (ref "U1") (pin "7") (pinfunction "XOUT_7") (pintype "bidirectional"))
    )
    (net (code "188") (name "unconnected-(X1G-B-Pad6)") (class "Default")
      (node (ref "X1") (pin "6") (pinfunction "B_6") (pintype "passive"))
    )
    (net (code "189") (name "unconnected-(X1H-B-Pad7)") (class "Default")
      (node (ref "X1") (pin "7") (pinfunction "B_7") (pintype "passive"))
    )
    (net (code "190") (name "unconnected-(X1I-B-Pad8)") (class "Default")
      (node (ref "X1") (pin "8") (pinfunction "B_8") (pintype "passive"))
    )
    (net (code "191") (name "~{D_HALT}") (class "Default")
      (node (ref "IC20") (pin "41") (pinfunction "PA20/SERCOM5_2/SERCOM3_2_41") (pintype "bidirectional"))
      (node (ref "IC9") (pin "51") (pinfunction "~{HALT}_51") (pintype "input"))
      (node (ref "U1") (pin "51") (pinfunction "~{HALT}_51") (pintype "bidirectional"))
    )
    (net (code "192") (name "~{D_INIT}") (class "Default")
      (node (ref "IC11") (pin "81") (pinfunction "P81_81") (pintype "bidirectional"))
      (node (ref "IC9") (pin "52") (pinfunction "~{INIT}_52") (pintype "input"))
    )
    (net (code "193") (name "~{D_IRL}") (class "Default")
      (node (ref "IC9") (pin "5") (pinfunction "IRL_5") (pintype "bidirectional"))
      (node (ref "U1") (pin "5") (pinfunction "IRL_5") (pintype "bidirectional"))
    )
    (net (code "194") (name "~{D_IRP}") (class "Default")
      (node (ref "IC11") (pin "55") (pinfunction "P55_55") (pintype "bidirectional"))
      (node (ref "IC9") (pin "4") (pinfunction "IRP_4") (pintype "bidirectional"))
      (node (ref "U1") (pin "4") (pinfunction "IRP_4") (pintype "bidirectional"))
    )
    (net (code "195") (name "~{D_NMI}") (class "Default")
      (node (ref "IC9") (pin "3") (pinfunction "~{NMI}_3") (pintype "input"))
      (node (ref "U1") (pin "3") (pinfunction "~{NMI}_3") (pintype "bidirectional"))
    )
    (net (code "196") (name "~{D_RD}") (class "Default")
      (node (ref "IC11") (pin "83") (pinfunction "P83_83") (pintype "bidirectional"))
      (node (ref "IC9") (pin "10") (pinfunction "IS/~{RD}_10") (pintype "output"))
    )
    (net (code "197") (name "~{D_TEST}") (class "Default")
      (node (ref "IC9") (pin "49") (pinfunction "~{TEST}_49") (pintype "input"))
      (node (ref "U1") (pin "49") (pinfunction "~{TEST}_49") (pintype "bidirectional"))
    )
    (net (code "198") (name "~{D_WDC}") (class "Default")
      (node (ref "IC9") (pin "53") (pinfunction "~{WDC}_53") (pintype "output"))
      (node (ref "U1") (pin "53") (pinfunction "WDC_53") (pintype "bidirectional"))
    )
    (net (code "199") (name "~{D_WI}") (class "Default")
      (node (ref "IC9") (pin "50") (pinfunction "~{WI}_50") (pintype "input"))
      (node (ref "U1") (pin "50") (pinfunction "~{WI}_50") (pintype "bidirectional"))
    )
    (net (code "200") (name "~{D_WR}") (class "Default")
      (node (ref "IC11") (pin "89") (pinfunction "P89/GCLK1_89") (pintype "input"))
      (node (ref "IC9") (pin "11") (pinfunction "OS/~{WR}_11") (pintype "output"))
    )
    (net (code "201") (name "~{E_INIT}") (class "Default")
      (node (ref "IC11") (pin "98") (pinfunction "P98_98") (pintype "bidirectional"))
      (node (ref "U1") (pin "52") (pinfunction "~{INIT}_52") (pintype "bidirectional"))
    )
    (net (code "202") (name "~{E_IS}") (class "Default")
      (node (ref "IC11") (pin "54") (pinfunction "P54_54") (pintype "bidirectional"))
      (node (ref "U1") (pin "10") (pinfunction "IS/~{RD}_10") (pintype "bidirectional"))
    )
    (net (code "203") (name "~{E_OS}") (class "Default")
      (node (ref "IC11") (pin "65") (pinfunction "P65_65") (pintype "bidirectional"))
      (node (ref "U1") (pin "11") (pinfunction "OS/~{WR}_11") (pintype "bidirectional"))
    )
    (net (code "204") (name "~{M_RAM_CS}") (class "Default")
      (node (ref "IC11") (pin "22") (pinfunction "P22_22") (pintype "bidirectional"))
      (node (ref "IC20") (pin "60") (pinfunction "PB31/SERCOM5_1_60") (pintype "bidirectional"))
      (node (ref "IC21") (pin "20") (pinfunction "~{CE}_20") (pintype "input"))
    )
    (net (code "205") (name "~{M_RD}") (class "Default")
      (node (ref "IC11") (pin "14") (pinfunction "P14_14") (pintype "bidirectional"))
      (node (ref "IC21") (pin "22") (pinfunction "~{OE}_22") (pintype "input"))
    )
    (net (code "206") (name "~{M_WR}") (class "Default")
      (node (ref "IC11") (pin "19") (pinfunction "P19_19") (pintype "bidirectional"))
      (node (ref "IC21") (pin "27") (pinfunction "~{WE}_27") (pintype "input"))
    )
    (net (code "207") (name "~{RESET}") (class "Default")
      (node (ref "IC20") (pin "52") (pinfunction "~{RESET}_52") (pintype "input"))
      (node (ref "X1") (pin "10") (pinfunction "B_10") (pintype "passive"))
    )
    (net (code "208") (name "~{X_INIT}") (class "Default")
      (node (ref "IC11") (pin "97") (pinfunction "P97_97") (pintype "bidirectional"))
      (node (ref "IC20") (pin "16") (pinfunction "PA07/SERCOM0_3_16") (pintype "bidirectional"))
    )
    (net (code "209") (name "~{X_INT}") (class "Default")
      (node (ref "R4") (pin "5") (pinfunction "2_5") (pintype "passive"))
      (node (ref "X2") (pin "2") (pinfunction "2_2") (pintype "passive"))
    )
    (net (code "210") (name "~{X_RD}") (class "Default")
      (node (ref "IC11") (pin "9") (pinfunction "P9_9") (pintype "bidirectional"))
      (node (ref "IC20") (pin "39") (pinfunction "PB16/SERCOM5_0_39") (pintype "bidirectional"))
    )
    (net (code "211") (name "~{X_WR}") (class "Default")
      (node (ref "IC11") (pin "13") (pinfunction "P13_13") (pintype "bidirectional"))
      (node (ref "IC20") (pin "40") (pinfunction "PB17/SERCOM5_1_40") (pintype "bidirectional"))
    )
  )
)
